# L6790A_GaN.net
KiCad netlist of a schematic drawn in Altium Designer
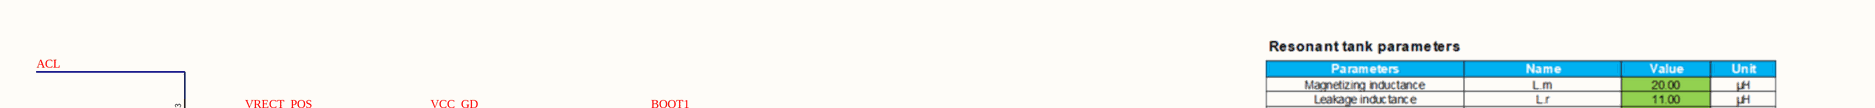
[diagram p0: L6790A_GaN.SchDoc, top left]
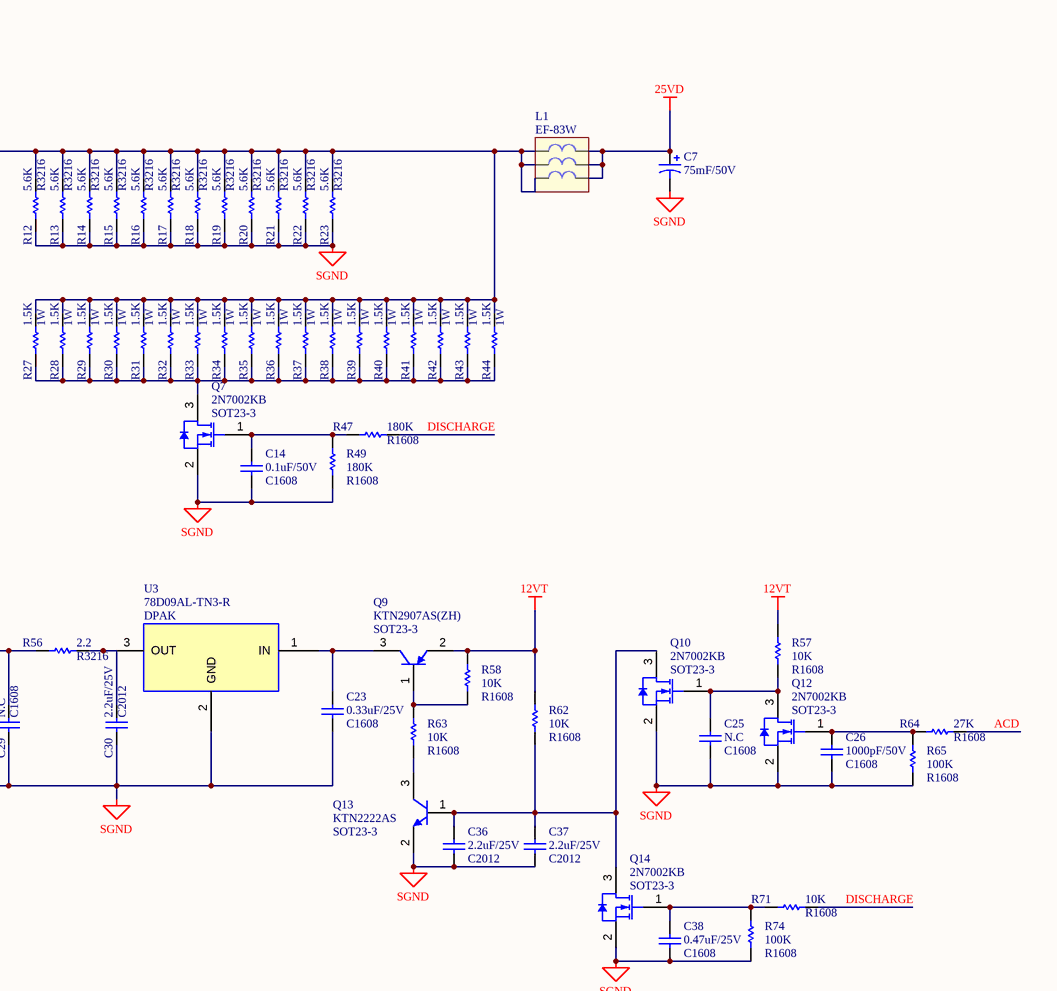
[diagram p1: L6790A_GaN.SchDoc, top right]
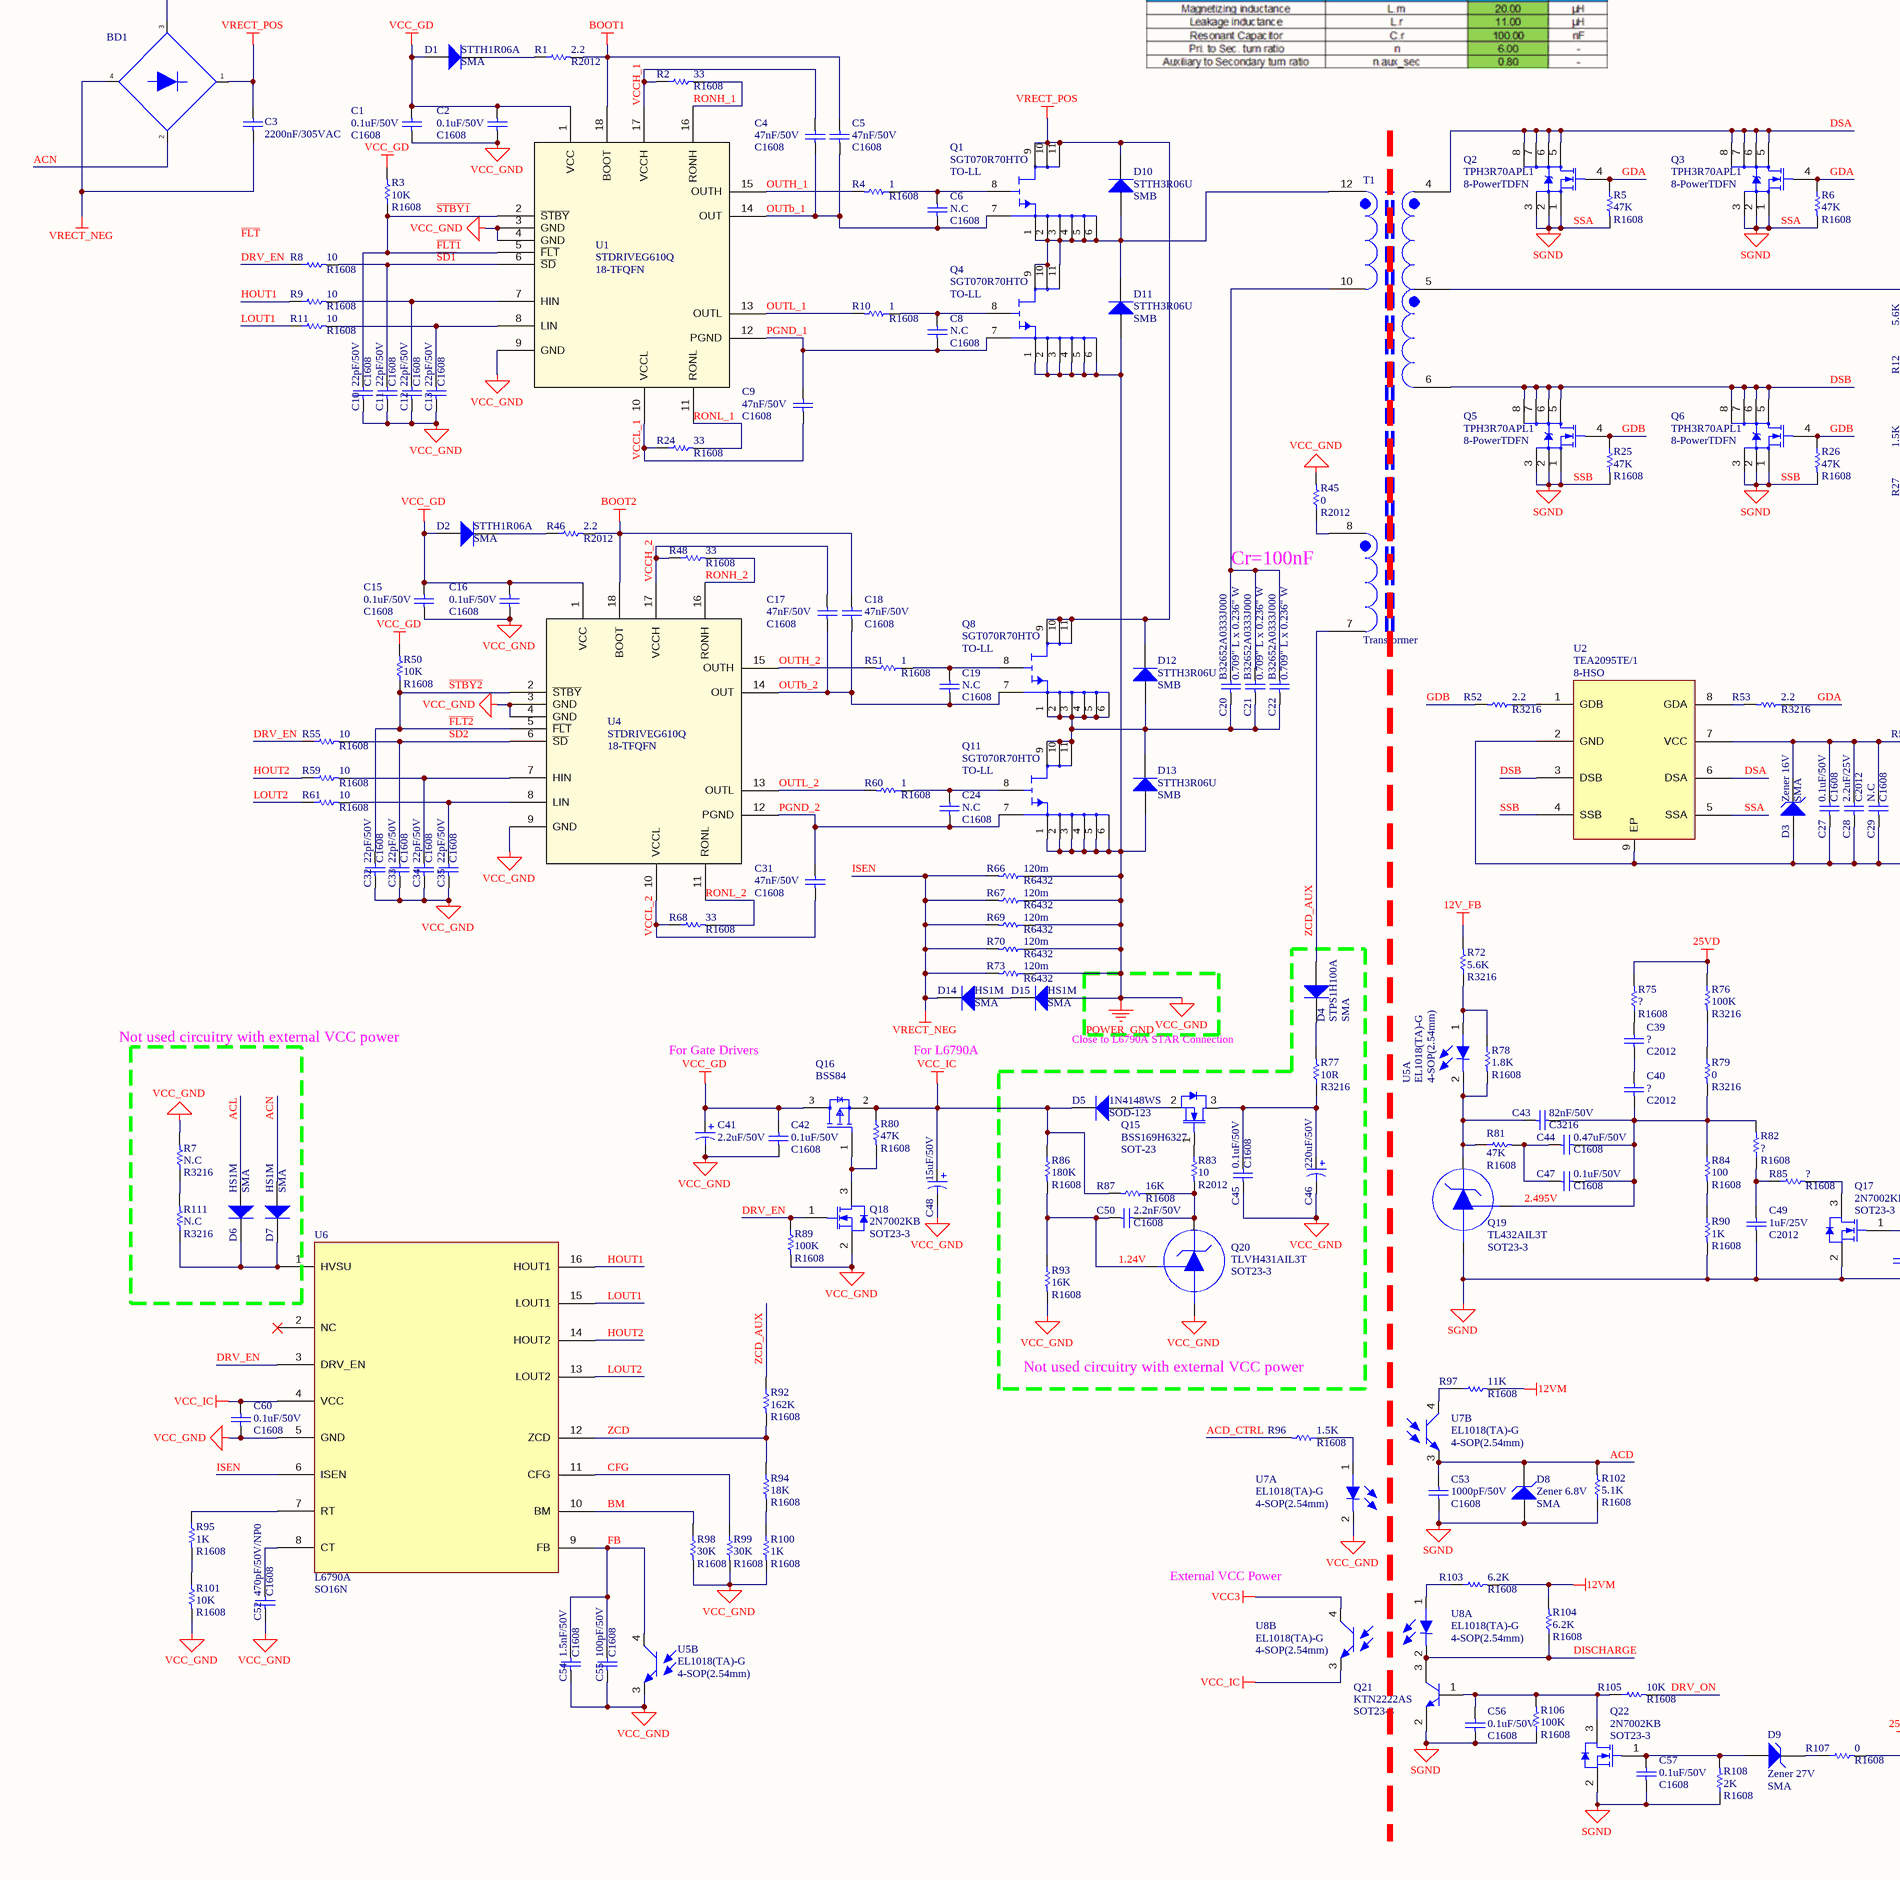
[diagram p2: L6790A_GaN.SchDoc, bottom left]
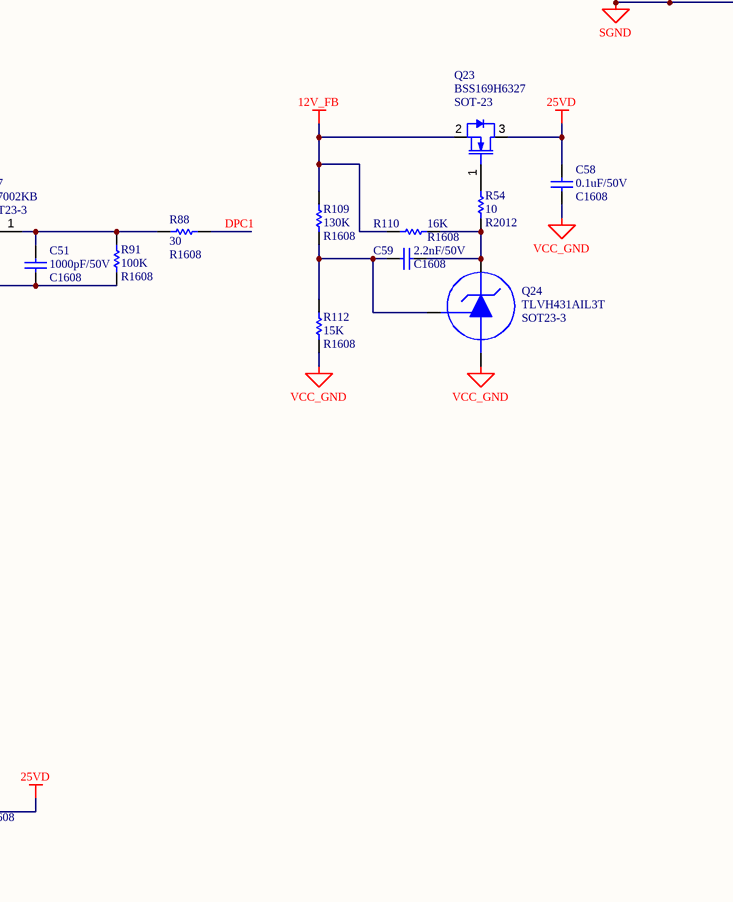
[diagram p3: L6790A_GaN.SchDoc, bottom right]

(export (version "E")
  (design (tool "Eeschema 10.0.6"))
  (components
    (comp (ref "BD1")
      (value "TS6KL60")
      (footprint "2W-DIO-MI-4L-4_6X25X15-7_5P-BD")
      (description "BRIDGE DIODE")
      (libsource (lib "Schematic") (part "BRIDGE"))
    )
    (comp (ref "C1")
      (value "0.1uF/50V")
      (description "Chip MLCC")
      (fields (field (name "PACKAGE/CASE") "C1608"))
      (libsource (lib "Miscellaneous Devices") (part "Cap"))
    )
    (comp (ref "C2")
      (value "0.1uF/50V")
      (description "Chip MLCC")
      (fields (field (name "PACKAGE/CASE") "C1608"))
      (libsource (lib "Miscellaneous Devices") (part "Cap"))
    )
    (comp (ref "C3")
      (value "2200nF/305VAC")
      (description "Chip MLCC")
      (libsource (lib "Miscellaneous Devices") (part "Cap"))
    )
    (comp (ref "C4")
      (value "47nF/50V")
      (description "Chip MLCC")
      (fields (field (name "PACKAGE/CASE") "C1608"))
      (libsource (lib "Miscellaneous Devices") (part "Cap"))
    )
    (comp (ref "C5")
      (value "47nF/50V")
      (description "Chip MLCC")
      (fields (field (name "PACKAGE/CASE") "C1608"))
      (libsource (lib "Miscellaneous Devices") (part "Cap"))
    )
    (comp (ref "C6")
      (value "N.C")
      (description "Chip MLCC")
      (fields (field (name "PACKAGE/CASE") "C1608"))
      (libsource (lib "Miscellaneous Devices") (part "Cap"))
    )
    (comp (ref "C7")
      (value "75mF/50V")
      (footprint "1W-CAP-MI-2L-16DX25-7_5P-EL-F-R1212")
      (description "Electrolytic Capacitor")
      (libsource (lib "Miscellaneous Devices") (part "Cap Pol1"))
    )
    (comp (ref "C8")
      (value "N.C")
      (description "Chip MLCC")
      (fields (field (name "PACKAGE/CASE") "C1608"))
      (libsource (lib "Miscellaneous Devices") (part "Cap"))
    )
    (comp (ref "C9")
      (value "47nF/50V")
      (description "Chip MLCC")
      (fields (field (name "PACKAGE/CASE") "C1608"))
      (libsource (lib "Miscellaneous Devices") (part "Cap"))
    )
    (comp (ref "C10")
      (value "22pF/50V")
      (description "Chip MLCC")
      (fields (field (name "PACKAGE/CASE") "C1608"))
      (libsource (lib "Miscellaneous Devices") (part "Cap"))
    )
    (comp (ref "C11")
      (value "22pF/50V")
      (description "Chip MLCC")
      (fields (field (name "PACKAGE/CASE") "C1608"))
      (libsource (lib "Miscellaneous Devices") (part "Cap"))
    )
    (comp (ref "C12")
      (value "22pF/50V")
      (description "Chip MLCC")
      (fields (field (name "PACKAGE/CASE") "C1608"))
      (libsource (lib "Miscellaneous Devices") (part "Cap"))
    )
    (comp (ref "C13")
      (value "22pF/50V")
      (description "Chip MLCC")
      (fields (field (name "PACKAGE/CASE") "C1608"))
      (libsource (lib "Miscellaneous Devices") (part "Cap"))
    )
    (comp (ref "C14")
      (value "0.1uF/50V")
      (description "Chip MLCC")
      (fields (field (name "PACKAGE/CASE") "C1608"))
      (libsource (lib "Miscellaneous Devices") (part "Cap"))
    )
    (comp (ref "C15")
      (value "0.1uF/50V")
      (description "Chip MLCC")
      (fields (field (name "PACKAGE/CASE") "C1608"))
      (libsource (lib "Miscellaneous Devices") (part "Cap"))
    )
    (comp (ref "C16")
      (value "0.1uF/50V")
      (description "Chip MLCC")
      (fields (field (name "PACKAGE/CASE") "C1608"))
      (libsource (lib "Miscellaneous Devices") (part "Cap"))
    )
    (comp (ref "C17")
      (value "47nF/50V")
      (description "Chip MLCC")
      (fields (field (name "PACKAGE/CASE") "C1608"))
      (libsource (lib "Miscellaneous Devices") (part "Cap"))
    )
    (comp (ref "C18")
      (value "47nF/50V")
      (description "Chip MLCC")
      (fields (field (name "PACKAGE/CASE") "C1608"))
      (libsource (lib "Miscellaneous Devices") (part "Cap"))
    )
    (comp (ref "C19")
      (value "N.C")
      (description "Chip MLCC")
      (fields (field (name "PACKAGE/CASE") "C1608"))
      (libsource (lib "Miscellaneous Devices") (part "Cap"))
    )
    (comp (ref "C20")
      (value "B32652A0333J000")
      (description "Chip MLCC")
      (fields (field (name "PACKAGE/CASE") "0.709\" L x 0.236\" W"))
      (libsource (lib "Miscellaneous Devices") (part "Cap"))
    )
    (comp (ref "C21")
      (value "B32652A0333J000")
      (description "Chip MLCC")
      (fields (field (name "PACKAGE/CASE") "0.709\" L x 0.236\" W"))
      (libsource (lib "Miscellaneous Devices") (part "Cap"))
    )
    (comp (ref "C22")
      (value "B32652A0333J000")
      (description "Chip MLCC")
      (fields (field (name "PACKAGE/CASE") "0.709\" L x 0.236\" W"))
      (libsource (lib "Miscellaneous Devices") (part "Cap"))
    )
    (comp (ref "C23")
      (value "0.33uF/25V")
      (description "Chip MLCC")
      (fields (field (name "PACKAGE/CASE") "C1608"))
      (libsource (lib "Miscellaneous Devices") (part "Cap"))
    )
    (comp (ref "C24")
      (value "N.C")
      (description "Chip MLCC")
      (fields (field (name "PACKAGE/CASE") "C1608"))
      (libsource (lib "Miscellaneous Devices") (part "Cap"))
    )
    (comp (ref "C25")
      (value "N.C")
      (description "Chip MLCC")
      (fields (field (name "PACKAGE/CASE") "C1608"))
      (libsource (lib "Miscellaneous Devices") (part "Cap"))
    )
    (comp (ref "C26")
      (value "1000pF/50V")
      (description "Chip MLCC")
      (fields (field (name "PACKAGE/CASE") "C1608"))
      (libsource (lib "Miscellaneous Devices") (part "Cap"))
    )
    (comp (ref "C27")
      (value "0.1uF/50V")
      (description "Chip MLCC")
      (fields (field (name "PACKAGE/CASE") "C1608"))
      (libsource (lib "Miscellaneous Devices") (part "Cap"))
    )
    (comp (ref "C28")
      (value "2.2uF/25V")
      (description "Chip MLCC")
      (fields (field (name "PACKAGE/CASE") "C2012"))
      (libsource (lib "Miscellaneous Devices") (part "Cap"))
    )
    (comp (ref "C29")
      (value "N.C")
      (description "Chip MLCC")
      (fields (field (name "PACKAGE/CASE") "C1608"))
      (libsource (lib "Miscellaneous Devices") (part "Cap"))
    )
    (comp (ref "C30")
      (value "2.2uF/25V")
      (description "Chip MLCC")
      (fields (field (name "PACKAGE/CASE") "C2012"))
      (libsource (lib "Miscellaneous Devices") (part "Cap"))
    )
    (comp (ref "C31")
      (value "47nF/50V")
      (description "Chip MLCC")
      (fields (field (name "PACKAGE/CASE") "C1608"))
      (libsource (lib "Miscellaneous Devices") (part "Cap"))
    )
    (comp (ref "C32")
      (value "22pF/50V")
      (description "Chip MLCC")
      (fields (field (name "PACKAGE/CASE") "C1608"))
      (libsource (lib "Miscellaneous Devices") (part "Cap"))
    )
    (comp (ref "C33")
      (value "22pF/50V")
      (description "Chip MLCC")
      (fields (field (name "PACKAGE/CASE") "C1608"))
      (libsource (lib "Miscellaneous Devices") (part "Cap"))
    )
    (comp (ref "C34")
      (value "22pF/50V")
      (description "Chip MLCC")
      (fields (field (name "PACKAGE/CASE") "C1608"))
      (libsource (lib "Miscellaneous Devices") (part "Cap"))
    )
    (comp (ref "C35")
      (value "22pF/50V")
      (description "Chip MLCC")
      (fields (field (name "PACKAGE/CASE") "C1608"))
      (libsource (lib "Miscellaneous Devices") (part "Cap"))
    )
    (comp (ref "C36")
      (value "2.2uF/25V")
      (description "Chip MLCC")
      (fields (field (name "PACKAGE/CASE") "C2012"))
      (libsource (lib "Miscellaneous Devices") (part "Cap"))
    )
    (comp (ref "C37")
      (value "2.2uF/25V")
      (description "Chip MLCC")
      (fields (field (name "PACKAGE/CASE") "C2012"))
      (libsource (lib "Miscellaneous Devices") (part "Cap"))
    )
    (comp (ref "C38")
      (value "0.47uF/25V")
      (description "Chip MLCC")
      (fields (field (name "PACKAGE/CASE") "C1608"))
      (libsource (lib "Miscellaneous Devices") (part "Cap"))
    )
    (comp (ref "C39")
      (value "?")
      (description "Chip MLCC")
      (fields (field (name "PACKAGE/CASE") "C2012"))
      (libsource (lib "Miscellaneous Devices") (part "Cap"))
    )
    (comp (ref "C40")
      (value "?")
      (description "Chip MLCC")
      (fields (field (name "PACKAGE/CASE") "C2012"))
      (libsource (lib "Miscellaneous Devices") (part "Cap"))
    )
    (comp (ref "C41")
      (value "2.2uF/50V")
      (footprint "CAP-RA-D5.0H12_5-P2-R0CA")
      (description "Electrolytic Capacitor 33uF/25V")
      (libsource (lib "Miscellaneous Devices") (part "Cap Pol1"))
    )
    (comp (ref "C42")
      (value "0.1uF/50V")
      (description "Chip MLCC")
      (fields (field (name "PACKAGE/CASE") "C1608"))
      (libsource (lib "Miscellaneous Devices") (part "Cap"))
    )
    (comp (ref "C43")
      (value "82nF/50V")
      (footprint "LGP55B_25U1_Y2S:CAP-CHP-3216-R0")
      (description "Chip MLCC")
      (fields (field (name "PACKAGE/CASE") "C3216"))
      (libsource (lib "Miscellaneous Devices") (part "Cap"))
    )
    (comp (ref "C44")
      (value "0.47uF/50V")
      (description "Chip MLCC")
      (fields (field (name "PACKAGE/CASE") "C1608"))
      (libsource (lib "Miscellaneous Devices") (part "Cap"))
    )
    (comp (ref "C45")
      (value "0.1uF/50V")
      (description "Chip MLCC")
      (fields (field (name "PACKAGE/CASE") "C1608"))
      (libsource (lib "Miscellaneous Devices") (part "Cap"))
    )
    (comp (ref "C46")
      (value "220uF/50V")
      (footprint "CAP-RA-D8H5-P2_5-R0")
      (description "Electrolytic Capacitor 22uF/100V")
      (libsource (lib "Miscellaneous Devices") (part "Cap Pol1"))
    )
    (comp (ref "C47")
      (value "0.1uF/50V")
      (description "Chip MLCC")
      (fields (field (name "PACKAGE/CASE") "C1608"))
      (libsource (lib "Miscellaneous Devices") (part "Cap"))
    )
    (comp (ref "C48")
      (value "15uF/50V")
      (footprint "CAP-RA-D5.0H12_5-P2-R0CA")
      (description "Electrolytic Capacitor 33uF/25V")
      (libsource (lib "Miscellaneous Devices") (part "Cap Pol1"))
    )
    (comp (ref "C49")
      (value "1uF/25V")
      (description "Chip MLCC")
      (fields (field (name "PACKAGE/CASE") "C2012"))
      (libsource (lib "Miscellaneous Devices") (part "Cap"))
    )
    (comp (ref "C50")
      (value "2.2nF/50V")
      (description "Chip MLCC")
      (fields (field (name "PACKAGE/CASE") "C1608"))
      (libsource (lib "Miscellaneous Devices") (part "Cap"))
    )
    (comp (ref "C51")
      (value "1000pF/50V")
      (description "Chip MLCC")
      (fields (field (name "PACKAGE/CASE") "C1608"))
      (libsource (lib "Miscellaneous Devices") (part "Cap"))
    )
    (comp (ref "C52")
      (value "470pF/50V/NP0")
      (description "Chip MLCC")
      (fields (field (name "PACKAGE/CASE") "C1608"))
      (libsource (lib "Miscellaneous Devices") (part "Cap"))
    )
    (comp (ref "C53")
      (value "1000pF/50V")
      (description "Chip MLCC")
      (fields (field (name "PACKAGE/CASE") "C1608"))
      (libsource (lib "Miscellaneous Devices") (part "Cap"))
    )
    (comp (ref "C54")
      (value "1.5nF/50V")
      (description "Chip MLCC")
      (fields (field (name "PACKAGE/CASE") "C1608"))
      (libsource (lib "Miscellaneous Devices") (part "Cap"))
    )
    (comp (ref "C55")
      (value "100pF/50V")
      (description "Chip MLCC")
      (fields (field (name "PACKAGE/CASE") "C1608"))
      (libsource (lib "Miscellaneous Devices") (part "Cap"))
    )
    (comp (ref "C56")
      (value "0.1uF/50V")
      (description "Chip MLCC")
      (fields (field (name "PACKAGE/CASE") "C1608"))
      (libsource (lib "Miscellaneous Devices") (part "Cap"))
    )
    (comp (ref "C57")
      (value "0.1uF/50V")
      (description "Chip MLCC")
      (fields (field (name "PACKAGE/CASE") "C1608"))
      (libsource (lib "Miscellaneous Devices") (part "Cap"))
    )
    (comp (ref "C58")
      (value "0.1uF/50V")
      (description "Chip MLCC")
      (fields (field (name "PACKAGE/CASE") "C1608"))
      (libsource (lib "Miscellaneous Devices") (part "Cap"))
    )
    (comp (ref "C59")
      (value "2.2nF/50V")
      (description "Chip MLCC")
      (fields (field (name "PACKAGE/CASE") "C1608"))
      (libsource (lib "Miscellaneous Devices") (part "Cap"))
    )
    (comp (ref "C60")
      (value "0.1uF/50V")
      (description "Chip MLCC")
      (fields (field (name "PACKAGE/CASE") "C1608"))
      (libsource (lib "Miscellaneous Devices") (part "Cap"))
    )
    (comp (ref "D1")
      (value "STTH1R06A")
      (footprint "DIO-SOD123")
      (description "DIODE SCHOTTKY 30V 200MA SOD123")
      (fields (field (name "PACKAGE/CASE") "SMA"))
      (libsource (lib "Miscellaneous Devices") (part "Diode 1N4148"))
    )
    (comp (ref "D2")
      (value "STTH1R06A")
      (footprint "DIO-SOD123")
      (description "DIODE SCHOTTKY 30V 200MA SOD123")
      (fields (field (name "PACKAGE/CASE") "SMA"))
      (libsource (lib "Miscellaneous Devices") (part "Diode 1N4148"))
    )
    (comp (ref "D3")
      (value "Zener 16V")
      (footprint "1W-DIO-CHP-2L-SOD106-SMA")
      (description "DIODE ZENER 30V 1W DO214AC")
      (fields (field (name "PACKAGE/CASE") "SMA"))
      (libsource (lib "Miscellaneous Devices") (part "D Zener"))
    )
    (comp (ref "D4")
      (value "STPS1H100A")
      (footprint "FP-6_560-5005_01-4-IPC_A")
      (description "DIODE STANDARD 200V 200MA SOD80")
      (fields (field (name "PACKAGE/CASE") "SMA"))
      (libsource (lib "Miscellaneous Devices") (part "Diode 1N4148"))
    )
    (comp (ref "D5")
      (value "1N4148WS")
      (footprint "DIO-SOD123")
      (description "DIODE SCHOTTKY 30V 200MA SOD123")
      (fields (field (name "PACKAGE/CASE") "SOD-123"))
      (libsource (lib "Miscellaneous Devices") (part "Diode 1N4148"))
    )
    (comp (ref "D6")
      (value "HS1M")
      (footprint "DIO-SOD123")
      (description "DIODE SCHOTTKY 30V 200MA SOD123")
      (fields (field (name "PACKAGE/CASE") "SMA"))
      (libsource (lib "Miscellaneous Devices") (part "Diode 1N4148"))
    )
    (comp (ref "D7")
      (value "HS1M")
      (footprint "DIO-SOD123")
      (description "DIODE SCHOTTKY 30V 200MA SOD123")
      (fields (field (name "PACKAGE/CASE") "SMA"))
      (libsource (lib "Miscellaneous Devices") (part "Diode 1N4148"))
    )
    (comp (ref "D8")
      (value "Zener 6.8V")
      (footprint "1W-DIO-CHP-2L-SOD106-SMA")
      (description "DIODE ZENER 30V 1W DO214AC")
      (fields (field (name "PACKAGE/CASE") "SMA"))
      (libsource (lib "Miscellaneous Devices") (part "D Zener"))
    )
    (comp (ref "D9")
      (value "Zener 27V")
      (footprint "1W-DIO-CHP-2L-SOD106-SMA")
      (description "DIODE ZENER 30V 1W DO214AC")
      (fields (field (name "PACKAGE/CASE") "SMA"))
      (libsource (lib "Miscellaneous Devices") (part "D Zener"))
    )
    (comp (ref "D10")
      (value "STTH3R06U")
      (footprint "DIO-SOD123")
      (description "DIODE SCHOTTKY 30V 200MA SOD123")
      (fields (field (name "PACKAGE/CASE") "SMB"))
      (libsource (lib "Miscellaneous Devices") (part "Diode 1N4148"))
    )
    (comp (ref "D11")
      (value "STTH3R06U")
      (footprint "DIO-SOD123")
      (description "DIODE SCHOTTKY 30V 200MA SOD123")
      (fields (field (name "PACKAGE/CASE") "SMB"))
      (libsource (lib "Miscellaneous Devices") (part "Diode 1N4148"))
    )
    (comp (ref "D12")
      (value "STTH3R06U")
      (footprint "DIO-SOD123")
      (description "DIODE SCHOTTKY 30V 200MA SOD123")
      (fields (field (name "PACKAGE/CASE") "SMB"))
      (libsource (lib "Miscellaneous Devices") (part "Diode 1N4148"))
    )
    (comp (ref "D13")
      (value "STTH3R06U")
      (footprint "DIO-SOD123")
      (description "DIODE SCHOTTKY 30V 200MA SOD123")
      (fields (field (name "PACKAGE/CASE") "SMB"))
      (libsource (lib "Miscellaneous Devices") (part "Diode 1N4148"))
    )
    (comp (ref "D14")
      (value "HS1M")
      (footprint "DIO-SOD123")
      (description "DIODE SCHOTTKY 30V 200MA SOD123")
      (fields (field (name "PACKAGE/CASE") "SMA"))
      (libsource (lib "Miscellaneous Devices") (part "Diode 1N4148"))
    )
    (comp (ref "D15")
      (value "HS1M")
      (footprint "DIO-SOD123")
      (description "DIODE SCHOTTKY 30V 200MA SOD123")
      (fields (field (name "PACKAGE/CASE") "SMA"))
      (libsource (lib "Miscellaneous Devices") (part "Diode 1N4148"))
    )
    (comp (ref "L1") (value "EF-83W") (libsource (lib "Schematic") (part "EF-83W")))
    (comp (ref "Q1")
      (value "SGT070R70HTO")
      (description "700 V, 53 mΩ typ., 26 A, e-mode PowerGaN transistor")
      (fields (field (name "PACKAGE/CASE") "TO-LL"))
      (libsource (lib "Schematic") (part "SGT070R70HTO"))
    )
    (comp (ref "Q2")
      (value "TPH3R70APL1")
      (description "N-Channel 100 V 90A (Tc) 210W (Tc) Surface Mount 8-SOP Advance (5x5.75)")
      (fields (field (name "PACKAGE/CASE") "8-PowerTDFN"))
      (libsource (lib "Schematic") (part "TPH3R70APL1"))
    )
    (comp (ref "Q3")
      (value "TPH3R70APL1")
      (description "N-Channel 100 V 90A (Tc) 210W (Tc) Surface Mount 8-SOP Advance (5x5.75)")
      (fields (field (name "PACKAGE/CASE") "8-PowerTDFN"))
      (libsource (lib "Schematic") (part "TPH3R70APL1"))
    )
    (comp (ref "Q4")
      (value "SGT070R70HTO")
      (description "700 V, 53 mΩ typ., 26 A, e-mode PowerGaN transistor")
      (fields (field (name "PACKAGE/CASE") "TO-LL"))
      (libsource (lib "Schematic") (part "SGT070R70HTO"))
    )
    (comp (ref "Q5")
      (value "TPH3R70APL1")
      (description "N-Channel 100 V 90A (Tc) 210W (Tc) Surface Mount 8-SOP Advance (5x5.75)")
      (fields (field (name "PACKAGE/CASE") "8-PowerTDFN"))
      (libsource (lib "Schematic") (part "TPH3R70APL1"))
    )
    (comp (ref "Q6")
      (value "TPH3R70APL1")
      (description "N-Channel 100 V 90A (Tc) 210W (Tc) Surface Mount 8-SOP Advance (5x5.75)")
      (fields (field (name "PACKAGE/CASE") "8-PowerTDFN"))
      (libsource (lib "Schematic") (part "TPH3R70APL1"))
    )
    (comp (ref "Q7")
      (value "2N7002KB")
      (description "N-CH MOSFET")
      (fields (field (name "PACKAGE/CASE") "SOT23-3"))
      (libsource (lib "Schematic") (part "2N7002KB"))
    )
    (comp (ref "Q8")
      (value "SGT070R70HTO")
      (description "700 V, 53 mΩ typ., 26 A, e-mode PowerGaN transistor")
      (fields (field (name "PACKAGE/CASE") "TO-LL"))
      (libsource (lib "Schematic") (part "SGT070R70HTO"))
    )
    (comp (ref "Q9")
      (value "KTN2907AS(ZH)")
      (description "PNP BJT")
      (fields (field (name "PACKAGE/CASE") "SOT23-3"))
      (libsource (lib "Schematic") (part "ONSC-PNP-B1E2C3-3"))
    )
    (comp (ref "Q10")
      (value "2N7002KB")
      (description "N-CH MOSFET")
      (fields (field (name "PACKAGE/CASE") "SOT23-3"))
      (libsource (lib "Schematic") (part "2N7002KB"))
    )
    (comp (ref "Q11")
      (value "SGT070R70HTO")
      (description "700 V, 53 mΩ typ., 26 A, e-mode PowerGaN transistor")
      (fields (field (name "PACKAGE/CASE") "TO-LL"))
      (libsource (lib "Schematic") (part "SGT070R70HTO"))
    )
    (comp (ref "Q12")
      (value "2N7002KB")
      (description "N-CH MOSFET")
      (fields (field (name "PACKAGE/CASE") "SOT23-3"))
      (libsource (lib "Schematic") (part "2N7002KB"))
    )
    (comp (ref "Q13")
      (value "KTN2222AS")
      (description "BJT NPN")
      (fields (field (name "PACKAGE/CASE") "SOT23-3"))
      (libsource (lib "Schematic") (part "ONSC-NPN-B1E2C3-3"))
    )
    (comp (ref "Q14")
      (value "2N7002KB")
      (description "N-CH MOSFET")
      (fields (field (name "PACKAGE/CASE") "SOT23-3"))
      (libsource (lib "Schematic") (part "2N7002KB"))
    )
    (comp (ref "Q15")
      (value "BSS169H6327")
      (footprint "SOT-23_TR")
      (description "MOSFET N-CH 100V 170MA SOT23-3")
      (fields (field (name "PACKAGE/CASE") "SOT-23"))
      (libsource (lib "Miscellaneous Devices") (part "CMP-32901-000982-1"))
    )
    (comp (ref "Q16")
      (value "BSS84")
      (footprint "FP-318-08-IPC_A")
      (description "MOSFET P-CH 50V 130MA SOT-23")
      (libsource (lib "Altium Content Vault") (part "1317a8eff0fddff9cd18bdaa032127a"))
    )
    (comp (ref "Q17")
      (value "2N7002KB")
      (description "N-CH MOSFET")
      (fields (field (name "PACKAGE/CASE") "SOT23-3"))
      (libsource (lib "Schematic") (part "2N7002KB"))
    )
    (comp (ref "Q18")
      (value "2N7002KB")
      (description "N-CH MOSFET")
      (fields (field (name "PACKAGE/CASE") "SOT23-3"))
      (libsource (lib "Schematic") (part "2N7002KB"))
    )
    (comp (ref "Q19")
      (value "TL432AIL3T")
      (footprint "SOT-23_TR")
      (description "IC VREF SHUNT ADJ 1% SOT23-3")
      (fields (field (name "PACKAGE/CASE") "SOT23-3"))
      (libsource (lib "*") (part "1W-IC-CHP-3L-SOT23-SCR-R0"))
    )
    (comp (ref "Q20")
      (value "TLVH431AIL3T")
      (footprint "SOT-23_TR")
      (description "IC VREF SHUNT ADJ 1% SOT23-3")
      (fields (field (name "PACKAGE/CASE") "SOT23-3"))
      (libsource (lib "*") (part "1W-IC-CHP-3L-SOT23-SCR-R0"))
    )
    (comp (ref "Q21")
      (value "KTN2222AS")
      (description "BJT NPN")
      (fields (field (name "PACKAGE/CASE") "SOT23-3"))
      (libsource (lib "Schematic") (part "ONSC-NPN-B1E2C3-3"))
    )
    (comp (ref "Q22")
      (value "2N7002KB")
      (description "N-CH MOSFET")
      (fields (field (name "PACKAGE/CASE") "SOT23-3"))
      (libsource (lib "Schematic") (part "2N7002KB"))
    )
    (comp (ref "Q23")
      (value "BSS169H6327")
      (footprint "SOT-23_TR")
      (description "MOSFET N-CH 100V 170MA SOT23-3")
      (fields (field (name "PACKAGE/CASE") "SOT-23"))
      (libsource (lib "Miscellaneous Devices") (part "CMP-32901-000982-1"))
    )
    (comp (ref "Q24")
      (value "TLVH431AIL3T")
      (footprint "SOT-23_TR")
      (description "IC VREF SHUNT ADJ 1% SOT23-3")
      (fields (field (name "PACKAGE/CASE") "SOT23-3"))
      (libsource (lib "*") (part "1W-IC-CHP-3L-SOT23-SCR-R0"))
    )
    (comp (ref "R1")
      (value "2.2")
      (footprint "RES-1608")
      (description "Chip Resistor")
      (fields (field (name "PACKAGE/CASE") "R2012"))
      (libsource (lib "Miscellaneous Devices") (part "Res1"))
    )
    (comp (ref "R2")
      (value "33")
      (footprint "RES-1608")
      (description "Chip Resistor")
      (fields (field (name "PACKAGE/CASE") "R1608"))
      (libsource (lib "Miscellaneous Devices") (part "Res1"))
    )
    (comp (ref "R3")
      (value "10K")
      (footprint "RES-1608")
      (description "Chip Resistor")
      (fields (field (name "PACKAGE/CASE") "R1608"))
      (libsource (lib "Miscellaneous Devices") (part "Res1"))
    )
    (comp (ref "R4")
      (value "1")
      (footprint "RES-1608")
      (description "Chip Resistor")
      (fields (field (name "PACKAGE/CASE") "R1608"))
      (libsource (lib "Miscellaneous Devices") (part "Res1"))
    )
    (comp (ref "R5")
      (value "47K")
      (footprint "RES-1608")
      (description "Chip Resistor")
      (fields (field (name "PACKAGE/CASE") "R1608"))
      (libsource (lib "Miscellaneous Devices") (part "Res1"))
    )
    (comp (ref "R6")
      (value "47K")
      (footprint "RES-1608")
      (description "Chip Resistor")
      (fields (field (name "PACKAGE/CASE") "R1608"))
      (libsource (lib "Miscellaneous Devices") (part "Res1"))
    )
    (comp (ref "R7")
      (value "N.C")
      (footprint "RES-3216")
      (description "Chip Resistor")
      (fields (field (name "PACKAGE/CASE") "R3216"))
      (libsource (lib "Miscellaneous Devices") (part "Res1"))
    )
    (comp (ref "R8")
      (value "10")
      (footprint "RES-1608")
      (description "Chip Resistor")
      (fields (field (name "PACKAGE/CASE") "R1608"))
      (libsource (lib "Miscellaneous Devices") (part "Res1"))
    )
    (comp (ref "R9")
      (value "10")
      (footprint "RES-1608")
      (description "Chip Resistor")
      (fields (field (name "PACKAGE/CASE") "R1608"))
      (libsource (lib "Miscellaneous Devices") (part "Res1"))
    )
    (comp (ref "R10")
      (value "1")
      (footprint "RES-1608")
      (description "Chip Resistor")
      (fields (field (name "PACKAGE/CASE") "R1608"))
      (libsource (lib "Miscellaneous Devices") (part "Res1"))
    )
    (comp (ref "R11")
      (value "10")
      (footprint "RES-1608")
      (description "Chip Resistor")
      (fields (field (name "PACKAGE/CASE") "R1608"))
      (libsource (lib "Miscellaneous Devices") (part "Res1"))
    )
    (comp (ref "R12")
      (value "5.6K")
      (footprint "RES-3216")
      (description "Chip Resistor")
      (fields (field (name "PACKAGE/CASE") "R3216"))
      (libsource (lib "Miscellaneous Devices") (part "Res1"))
    )
    (comp (ref "R13")
      (value "5.6K")
      (footprint "RES-3216")
      (description "Chip Resistor")
      (fields (field (name "PACKAGE/CASE") "R3216"))
      (libsource (lib "Miscellaneous Devices") (part "Res1"))
    )
    (comp (ref "R14")
      (value "5.6K")
      (footprint "RES-3216")
      (description "Chip Resistor")
      (fields (field (name "PACKAGE/CASE") "R3216"))
      (libsource (lib "Miscellaneous Devices") (part "Res1"))
    )
    (comp (ref "R15")
      (value "5.6K")
      (footprint "RES-3216")
      (description "Chip Resistor")
      (fields (field (name "PACKAGE/CASE") "R3216"))
      (libsource (lib "Miscellaneous Devices") (part "Res1"))
    )
    (comp (ref "R16")
      (value "5.6K")
      (footprint "RES-3216")
      (description "Chip Resistor")
      (fields (field (name "PACKAGE/CASE") "R3216"))
      (libsource (lib "Miscellaneous Devices") (part "Res1"))
    )
    (comp (ref "R17")
      (value "5.6K")
      (footprint "RES-3216")
      (description "Chip Resistor")
      (fields (field (name "PACKAGE/CASE") "R3216"))
      (libsource (lib "Miscellaneous Devices") (part "Res1"))
    )
    (comp (ref "R18")
      (value "5.6K")
      (footprint "RES-3216")
      (description "Chip Resistor")
      (fields (field (name "PACKAGE/CASE") "R3216"))
      (libsource (lib "Miscellaneous Devices") (part "Res1"))
    )
    (comp (ref "R19")
      (value "5.6K")
      (footprint "RES-3216")
      (description "Chip Resistor")
      (fields (field (name "PACKAGE/CASE") "R3216"))
      (libsource (lib "Miscellaneous Devices") (part "Res1"))
    )
    (comp (ref "R20")
      (value "5.6K")
      (footprint "RES-3216")
      (description "Chip Resistor")
      (fields (field (name "PACKAGE/CASE") "R3216"))
      (libsource (lib "Miscellaneous Devices") (part "Res1"))
    )
    (comp (ref "R21")
      (value "5.6K")
      (footprint "RES-3216")
      (description "Chip Resistor")
      (fields (field (name "PACKAGE/CASE") "R3216"))
      (libsource (lib "Miscellaneous Devices") (part "Res1"))
    )
    (comp (ref "R22")
      (value "5.6K")
      (footprint "RES-3216")
      (description "Chip Resistor")
      (fields (field (name "PACKAGE/CASE") "R3216"))
      (libsource (lib "Miscellaneous Devices") (part "Res1"))
    )
    (comp (ref "R23")
      (value "5.6K")
      (footprint "RES-3216")
      (description "Chip Resistor")
      (fields (field (name "PACKAGE/CASE") "R3216"))
      (libsource (lib "Miscellaneous Devices") (part "Res1"))
    )
    (comp (ref "R24")
      (value "33")
      (footprint "RES-1608")
      (description "Chip Resistor")
      (fields (field (name "PACKAGE/CASE") "R1608"))
      (libsource (lib "Miscellaneous Devices") (part "Res1"))
    )
    (comp (ref "R25")
      (value "47K")
      (footprint "RES-1608")
      (description "Chip Resistor")
      (fields (field (name "PACKAGE/CASE") "R1608"))
      (libsource (lib "Miscellaneous Devices") (part "Res1"))
    )
    (comp (ref "R26")
      (value "47K")
      (footprint "RES-1608")
      (description "Chip Resistor")
      (fields (field (name "PACKAGE/CASE") "R1608"))
      (libsource (lib "Miscellaneous Devices") (part "Res1"))
    )
    (comp (ref "R27")
      (value "1.5K")
      (description "Watt Resistor")
      (fields (field (name "PACKAGE/CASE") "1W"))
      (libsource (lib "Miscellaneous Devices") (part "Res1"))
    )
    (comp (ref "R28")
      (value "1.5K")
      (description "Watt Resistor")
      (fields (field (name "PACKAGE/CASE") "1W"))
      (libsource (lib "Miscellaneous Devices") (part "Res1"))
    )
    (comp (ref "R29")
      (value "1.5K")
      (description "Watt Resistor")
      (fields (field (name "PACKAGE/CASE") "1W"))
      (libsource (lib "Miscellaneous Devices") (part "Res1"))
    )
    (comp (ref "R30")
      (value "1.5K")
      (description "Watt Resistor")
      (fields (field (name "PACKAGE/CASE") "1W"))
      (libsource (lib "Miscellaneous Devices") (part "Res1"))
    )
    (comp (ref "R31")
      (value "1.5K")
      (description "Watt Resistor")
      (fields (field (name "PACKAGE/CASE") "1W"))
      (libsource (lib "Miscellaneous Devices") (part "Res1"))
    )
    (comp (ref "R32")
      (value "1.5K")
      (description "Watt Resistor")
      (fields (field (name "PACKAGE/CASE") "1W"))
      (libsource (lib "Miscellaneous Devices") (part "Res1"))
    )
    (comp (ref "R33")
      (value "1.5K")
      (description "Watt Resistor")
      (fields (field (name "PACKAGE/CASE") "1W"))
      (libsource (lib "Miscellaneous Devices") (part "Res1"))
    )
    (comp (ref "R34")
      (value "1.5K")
      (description "Watt Resistor")
      (fields (field (name "PACKAGE/CASE") "1W"))
      (libsource (lib "Miscellaneous Devices") (part "Res1"))
    )
    (comp (ref "R35")
      (value "1.5K")
      (description "Watt Resistor")
      (fields (field (name "PACKAGE/CASE") "1W"))
      (libsource (lib "Miscellaneous Devices") (part "Res1"))
    )
    (comp (ref "R36")
      (value "1.5K")
      (description "Watt Resistor")
      (fields (field (name "PACKAGE/CASE") "1W"))
      (libsource (lib "Miscellaneous Devices") (part "Res1"))
    )
    (comp (ref "R37")
      (value "1.5K")
      (description "Watt Resistor")
      (fields (field (name "PACKAGE/CASE") "1W"))
      (libsource (lib "Miscellaneous Devices") (part "Res1"))
    )
    (comp (ref "R38")
      (value "1.5K")
      (description "Watt Resistor")
      (fields (field (name "PACKAGE/CASE") "1W"))
      (libsource (lib "Miscellaneous Devices") (part "Res1"))
    )
    (comp (ref "R39")
      (value "1.5K")
      (description "Watt Resistor")
      (fields (field (name "PACKAGE/CASE") "1W"))
      (libsource (lib "Miscellaneous Devices") (part "Res1"))
    )
    (comp (ref "R40")
      (value "1.5K")
      (description "Watt Resistor")
      (fields (field (name "PACKAGE/CASE") "1W"))
      (libsource (lib "Miscellaneous Devices") (part "Res1"))
    )
    (comp (ref "R41")
      (value "1.5K")
      (description "Watt Resistor")
      (fields (field (name "PACKAGE/CASE") "1W"))
      (libsource (lib "Miscellaneous Devices") (part "Res1"))
    )
    (comp (ref "R42")
      (value "1.5K")
      (description "Watt Resistor")
      (fields (field (name "PACKAGE/CASE") "1W"))
      (libsource (lib "Miscellaneous Devices") (part "Res1"))
    )
    (comp (ref "R43")
      (value "1.5K")
      (description "Watt Resistor")
      (fields (field (name "PACKAGE/CASE") "1W"))
      (libsource (lib "Miscellaneous Devices") (part "Res1"))
    )
    (comp (ref "R44")
      (value "1.5K")
      (description "Watt Resistor")
      (fields (field (name "PACKAGE/CASE") "1W"))
      (libsource (lib "Miscellaneous Devices") (part "Res1"))
    )
    (comp (ref "R45")
      (value "0")
      (footprint "RES-1608")
      (description "Chip Resistor")
      (fields (field (name "PACKAGE/CASE") "R2012"))
      (libsource (lib "Miscellaneous Devices") (part "Res1"))
    )
    (comp (ref "R46")
      (value "2.2")
      (footprint "RES-1608")
      (description "Chip Resistor")
      (fields (field (name "PACKAGE/CASE") "R2012"))
      (libsource (lib "Miscellaneous Devices") (part "Res1"))
    )
    (comp (ref "R47")
      (value "180K")
      (footprint "RES-1608")
      (description "Chip Resistor")
      (fields (field (name "PACKAGE/CASE") "R1608"))
      (libsource (lib "Miscellaneous Devices") (part "Res1"))
    )
    (comp (ref "R48")
      (value "33")
      (footprint "RES-1608")
      (description "Chip Resistor")
      (fields (field (name "PACKAGE/CASE") "R1608"))
      (libsource (lib "Miscellaneous Devices") (part "Res1"))
    )
    (comp (ref "R49")
      (value "180K")
      (footprint "RES-1608")
      (description "Chip Resistor")
      (fields (field (name "PACKAGE/CASE") "R1608"))
      (libsource (lib "Miscellaneous Devices") (part "Res1"))
    )
    (comp (ref "R50")
      (value "10K")
      (footprint "RES-1608")
      (description "Chip Resistor")
      (fields (field (name "PACKAGE/CASE") "R1608"))
      (libsource (lib "Miscellaneous Devices") (part "Res1"))
    )
    (comp (ref "R51")
      (value "1")
      (footprint "RES-1608")
      (description "Chip Resistor")
      (fields (field (name "PACKAGE/CASE") "R1608"))
      (libsource (lib "Miscellaneous Devices") (part "Res1"))
    )
    (comp (ref "R52")
      (value "2.2")
      (footprint "RES-3216")
      (description "Chip Resistor")
      (fields (field (name "PACKAGE/CASE") "R3216"))
      (libsource (lib "Miscellaneous Devices") (part "Res1"))
    )
    (comp (ref "R53")
      (value "2.2")
      (footprint "RES-3216")
      (description "Chip Resistor")
      (fields (field (name "PACKAGE/CASE") "R3216"))
      (libsource (lib "Miscellaneous Devices") (part "Res1"))
    )
    (comp (ref "R54")
      (value "10")
      (footprint "RES-1608")
      (description "Chip Resistor")
      (fields (field (name "PACKAGE/CASE") "R2012"))
      (libsource (lib "Miscellaneous Devices") (part "Res1"))
    )
    (comp (ref "R55")
      (value "10")
      (footprint "RES-1608")
      (description "Chip Resistor")
      (fields (field (name "PACKAGE/CASE") "R1608"))
      (libsource (lib "Miscellaneous Devices") (part "Res1"))
    )
    (comp (ref "R56")
      (value "2.2")
      (footprint "RES-3216")
      (description "Chip Resistor")
      (fields (field (name "PACKAGE/CASE") "R3216"))
      (libsource (lib "Miscellaneous Devices") (part "Res1"))
    )
    (comp (ref "R57")
      (value "10K")
      (footprint "RES-1608")
      (description "Chip Resistor")
      (fields (field (name "PACKAGE/CASE") "R1608"))
      (libsource (lib "Miscellaneous Devices") (part "Res1"))
    )
    (comp (ref "R58")
      (value "10K")
      (footprint "RES-1608")
      (description "Chip Resistor")
      (fields (field (name "PACKAGE/CASE") "R1608"))
      (libsource (lib "Miscellaneous Devices") (part "Res1"))
    )
    (comp (ref "R59")
      (value "10")
      (footprint "RES-1608")
      (description "Chip Resistor")
      (fields (field (name "PACKAGE/CASE") "R1608"))
      (libsource (lib "Miscellaneous Devices") (part "Res1"))
    )
    (comp (ref "R60")
      (value "1")
      (footprint "RES-1608")
      (description "Chip Resistor")
      (fields (field (name "PACKAGE/CASE") "R1608"))
      (libsource (lib "Miscellaneous Devices") (part "Res1"))
    )
    (comp (ref "R61")
      (value "10")
      (footprint "RES-1608")
      (description "Chip Resistor")
      (fields (field (name "PACKAGE/CASE") "R1608"))
      (libsource (lib "Miscellaneous Devices") (part "Res1"))
    )
    (comp (ref "R62")
      (value "10K")
      (footprint "RES-1608")
      (description "Chip Resistor")
      (fields (field (name "PACKAGE/CASE") "R1608"))
      (libsource (lib "Miscellaneous Devices") (part "Res1"))
    )
    (comp (ref "R63")
      (value "10K")
      (footprint "RES-1608")
      (description "Chip Resistor")
      (fields (field (name "PACKAGE/CASE") "R1608"))
      (libsource (lib "Miscellaneous Devices") (part "Res1"))
    )
    (comp (ref "R64")
      (value "27K")
      (footprint "RES-1608")
      (description "Chip Resistor")
      (fields (field (name "PACKAGE/CASE") "R1608"))
      (libsource (lib "Miscellaneous Devices") (part "Res1"))
    )
    (comp (ref "R65")
      (value "100K")
      (footprint "RES-1608")
      (description "Chip Resistor")
      (fields (field (name "PACKAGE/CASE") "R1608"))
      (libsource (lib "Miscellaneous Devices") (part "Res1"))
    )
    (comp (ref "R66")
      (value "120m")
      (description "Chip Resistor")
      (fields (field (name "PACKAGE/CASE") "R6432"))
      (libsource (lib "Miscellaneous Devices") (part "Res1"))
    )
    (comp (ref "R67")
      (value "120m")
      (description "Chip Resistor")
      (fields (field (name "PACKAGE/CASE") "R6432"))
      (libsource (lib "Miscellaneous Devices") (part "Res1"))
    )
    (comp (ref "R68")
      (value "33")
      (footprint "RES-1608")
      (description "Chip Resistor")
      (fields (field (name "PACKAGE/CASE") "R1608"))
      (libsource (lib "Miscellaneous Devices") (part "Res1"))
    )
    (comp (ref "R69")
      (value "120m")
      (description "Chip Resistor")
      (fields (field (name "PACKAGE/CASE") "R6432"))
      (libsource (lib "Miscellaneous Devices") (part "Res1"))
    )
    (comp (ref "R70")
      (value "120m")
      (description "Chip Resistor")
      (fields (field (name "PACKAGE/CASE") "R6432"))
      (libsource (lib "Miscellaneous Devices") (part "Res1"))
    )
    (comp (ref "R71")
      (value "10K")
      (footprint "RES-1608")
      (description "Chip Resistor")
      (fields (field (name "PACKAGE/CASE") "R1608"))
      (libsource (lib "Miscellaneous Devices") (part "Res1"))
    )
    (comp (ref "R72")
      (value "5.6K")
      (footprint "RES-3216")
      (description "Chip Resistor")
      (fields (field (name "PACKAGE/CASE") "R3216"))
      (libsource (lib "Miscellaneous Devices") (part "Res1"))
    )
    (comp (ref "R73")
      (value "120m")
      (description "Chip Resistor")
      (fields (field (name "PACKAGE/CASE") "R6432"))
      (libsource (lib "Miscellaneous Devices") (part "Res1"))
    )
    (comp (ref "R74")
      (value "100K")
      (footprint "RES-1608")
      (description "Chip Resistor")
      (fields (field (name "PACKAGE/CASE") "R1608"))
      (libsource (lib "Miscellaneous Devices") (part "Res1"))
    )
    (comp (ref "R75")
      (value "?")
      (footprint "RES-1608")
      (description "Chip Resistor")
      (fields (field (name "PACKAGE/CASE") "R1608"))
      (libsource (lib "Miscellaneous Devices") (part "Res1"))
    )
    (comp (ref "R76")
      (value "100K")
      (footprint "RES-3216")
      (description "Chip Resistor")
      (fields (field (name "PACKAGE/CASE") "R3216"))
      (libsource (lib "Miscellaneous Devices") (part "Res1"))
    )
    (comp (ref "R77")
      (value "10R")
      (footprint "RES-3216")
      (description "Chip Resistor")
      (fields (field (name "PACKAGE/CASE") "R3216"))
      (libsource (lib "Miscellaneous Devices") (part "Res1"))
    )
    (comp (ref "R78")
      (value "1.8K")
      (footprint "RES-1608")
      (description "Chip Resistor")
      (fields (field (name "PACKAGE/CASE") "R1608"))
      (libsource (lib "Miscellaneous Devices") (part "Res1"))
    )
    (comp (ref "R79")
      (value "0")
      (footprint "RES-3216")
      (description "Chip Resistor")
      (fields (field (name "PACKAGE/CASE") "R3216"))
      (libsource (lib "Miscellaneous Devices") (part "Res1"))
    )
    (comp (ref "R80")
      (value "47K")
      (footprint "RES-1608")
      (description "Chip Resistor")
      (fields (field (name "PACKAGE/CASE") "R1608"))
      (libsource (lib "Miscellaneous Devices") (part "Res1"))
    )
    (comp (ref "R81")
      (value "47K")
      (footprint "RES-1608")
      (description "Chip Resistor")
      (fields (field (name "PACKAGE/CASE") "R1608"))
      (libsource (lib "Miscellaneous Devices") (part "Res1"))
    )
    (comp (ref "R82")
      (value "?")
      (footprint "RES-1608")
      (description "Chip Resistor")
      (fields (field (name "PACKAGE/CASE") "R1608"))
      (libsource (lib "Miscellaneous Devices") (part "Res1"))
    )
    (comp (ref "R83")
      (value "10")
      (footprint "RES-1608")
      (description "Chip Resistor")
      (fields (field (name "PACKAGE/CASE") "R2012"))
      (libsource (lib "Miscellaneous Devices") (part "Res1"))
    )
    (comp (ref "R84")
      (value "100")
      (footprint "RES-1608")
      (description "Chip Resistor")
      (fields (field (name "PACKAGE/CASE") "R1608"))
      (libsource (lib "Miscellaneous Devices") (part "Res1"))
    )
    (comp (ref "R85")
      (value "?")
      (footprint "RES-1608")
      (description "Chip Resistor")
      (fields (field (name "PACKAGE/CASE") "R1608"))
      (libsource (lib "Miscellaneous Devices") (part "Res1"))
    )
    (comp (ref "R86")
      (value "180K")
      (footprint "RES-1608")
      (description "Chip Resistor")
      (fields (field (name "PACKAGE/CASE") "R1608"))
      (libsource (lib "Miscellaneous Devices") (part "Res1"))
    )
    (comp (ref "R87")
      (value "16K")
      (footprint "RES-1608")
      (description "Chip Resistor")
      (fields (field (name "PACKAGE/CASE") "R1608"))
      (libsource (lib "Miscellaneous Devices") (part "Res1"))
    )
    (comp (ref "R88")
      (value "30")
      (footprint "RES-1608")
      (description "Chip Resistor")
      (fields (field (name "PACKAGE/CASE") "R1608"))
      (libsource (lib "Miscellaneous Devices") (part "Res1"))
    )
    (comp (ref "R89")
      (value "100K")
      (footprint "RES-1608")
      (description "Chip Resistor")
      (fields (field (name "PACKAGE/CASE") "R1608"))
      (libsource (lib "Miscellaneous Devices") (part "Res1"))
    )
    (comp (ref "R90")
      (value "1K")
      (footprint "RES-1608")
      (description "Chip Resistor")
      (fields (field (name "PACKAGE/CASE") "R1608"))
      (libsource (lib "Miscellaneous Devices") (part "Res1"))
    )
    (comp (ref "R91")
      (value "100K")
      (footprint "RES-1608")
      (description "Chip Resistor")
      (fields (field (name "PACKAGE/CASE") "R1608"))
      (libsource (lib "Miscellaneous Devices") (part "Res1"))
    )
    (comp (ref "R92")
      (value "162K")
      (footprint "RES-1608")
      (description "Chip Resistor")
      (fields (field (name "PACKAGE/CASE") "R1608"))
      (libsource (lib "Miscellaneous Devices") (part "Res1"))
    )
    (comp (ref "R93")
      (value "16K")
      (footprint "RES-1608")
      (description "Chip Resistor")
      (fields (field (name "PACKAGE/CASE") "R1608"))
      (libsource (lib "Miscellaneous Devices") (part "Res1"))
    )
    (comp (ref "R94")
      (value "18K")
      (footprint "RES-1608")
      (description "Chip Resistor")
      (fields (field (name "PACKAGE/CASE") "R1608"))
      (libsource (lib "Miscellaneous Devices") (part "Res1"))
    )
    (comp (ref "R95")
      (value "1K")
      (footprint "RES-1608")
      (description "Chip Resistor")
      (fields (field (name "PACKAGE/CASE") "R1608"))
      (libsource (lib "Miscellaneous Devices") (part "Res1"))
    )
    (comp (ref "R96")
      (value "1.5K")
      (footprint "RES-1608")
      (description "Chip Resistor")
      (fields (field (name "PACKAGE/CASE") "R1608"))
      (libsource (lib "Miscellaneous Devices") (part "Res1"))
    )
    (comp (ref "R97")
      (value "11K")
      (footprint "RES-1608")
      (description "Chip Resistor")
      (fields (field (name "PACKAGE/CASE") "R1608"))
      (libsource (lib "Miscellaneous Devices") (part "Res1"))
    )
    (comp (ref "R98")
      (value "30K")
      (footprint "RES-1608")
      (description "Chip Resistor")
      (fields (field (name "PACKAGE/CASE") "R1608"))
      (libsource (lib "Miscellaneous Devices") (part "Res1"))
    )
    (comp (ref "R99")
      (value "30K")
      (footprint "RES-1608")
      (description "Chip Resistor")
      (fields (field (name "PACKAGE/CASE") "R1608"))
      (libsource (lib "Miscellaneous Devices") (part "Res1"))
    )
    (comp (ref "R100")
      (value "1K")
      (footprint "RES-1608")
      (description "Chip Resistor")
      (fields (field (name "PACKAGE/CASE") "R1608"))
      (libsource (lib "Miscellaneous Devices") (part "Res1"))
    )
    (comp (ref "R101")
      (value "10K")
      (footprint "RES-1608")
      (description "Chip Resistor")
      (fields (field (name "PACKAGE/CASE") "R1608"))
      (libsource (lib "Miscellaneous Devices") (part "Res1"))
    )
    (comp (ref "R102")
      (value "5.1K")
      (footprint "RES-1608")
      (description "Chip Resistor")
      (fields (field (name "PACKAGE/CASE") "R1608"))
      (libsource (lib "Miscellaneous Devices") (part "Res1"))
    )
    (comp (ref "R103")
      (value "6.2K")
      (footprint "RES-1608")
      (description "Chip Resistor")
      (fields (field (name "PACKAGE/CASE") "R1608"))
      (libsource (lib "Miscellaneous Devices") (part "Res1"))
    )
    (comp (ref "R104")
      (value "6.2K")
      (footprint "RES-1608")
      (description "Chip Resistor")
      (fields (field (name "PACKAGE/CASE") "R1608"))
      (libsource (lib "Miscellaneous Devices") (part "Res1"))
    )
    (comp (ref "R105")
      (value "10K")
      (footprint "RES-1608")
      (description "Chip Resistor")
      (fields (field (name "PACKAGE/CASE") "R1608"))
      (libsource (lib "Miscellaneous Devices") (part "Res1"))
    )
    (comp (ref "R106")
      (value "100K")
      (footprint "RES-1608")
      (description "Chip Resistor")
      (fields (field (name "PACKAGE/CASE") "R1608"))
      (libsource (lib "Miscellaneous Devices") (part "Res1"))
    )
    (comp (ref "R107")
      (value "0")
      (footprint "RES-1608")
      (description "Chip Resistor")
      (fields (field (name "PACKAGE/CASE") "R1608"))
      (libsource (lib "Miscellaneous Devices") (part "Res1"))
    )
    (comp (ref "R108")
      (value "2K")
      (footprint "RES-1608")
      (description "Chip Resistor")
      (fields (field (name "PACKAGE/CASE") "R1608"))
      (libsource (lib "Miscellaneous Devices") (part "Res1"))
    )
    (comp (ref "R109")
      (value "130K")
      (footprint "RES-1608")
      (description "Chip Resistor")
      (fields (field (name "PACKAGE/CASE") "R1608"))
      (libsource (lib "Miscellaneous Devices") (part "Res1"))
    )
    (comp (ref "R110")
      (value "16K")
      (footprint "RES-1608")
      (description "Chip Resistor")
      (fields (field (name "PACKAGE/CASE") "R1608"))
      (libsource (lib "Miscellaneous Devices") (part "Res1"))
    )
    (comp (ref "R111")
      (value "N.C")
      (footprint "RES-3216")
      (description "Chip Resistor")
      (fields (field (name "PACKAGE/CASE") "R3216"))
      (libsource (lib "Miscellaneous Devices") (part "Res1"))
    )
    (comp (ref "R112")
      (value "15K")
      (footprint "RES-1608")
      (description "Chip Resistor")
      (fields (field (name "PACKAGE/CASE") "R1608"))
      (libsource (lib "Miscellaneous Devices") (part "Res1"))
    )
    (comp (ref "T1") (value "Transformer") (libsource (lib "Schematic") (part "Transformer")))
    (comp (ref "U1")
      (value "STDRIVEG610Q")
      (description "High voltage and high-speed half-bridge gate driver for GaN power switches")
      (fields (field (name "PACKAGE/CASE") "18-TFQFN"))
      (libsource (lib "Schematic") (part "STDRIVEG610Q"))
    )
    (comp (ref "U2")
      (value "TEA2095TE/1")
      (description "LLC SR CONTROLLER IC")
      (fields (field (name "PACKAGE/CASE") "8-HSO"))
      (libsource (lib "Schematic") (part "TEA2095TE/1"))
    )
    (comp (ref "U3")
      (value "78D09AL-TN3-R")
      (description "3-TERMINALS 1A POSITIVE VOLTAGE REGULATOR")
      (fields (field (name "PACKAGE/CASE") "DPAK"))
      (libsource (lib "Schematic") (part "78D09AL-TN3-R"))
    )
    (comp (ref "U4")
      (value "STDRIVEG610Q")
      (description "High voltage and high-speed half-bridge gate driver for GaN power switches")
      (fields (field (name "PACKAGE/CASE") "18-TFQFN"))
      (libsource (lib "Schematic") (part "STDRIVEG610Q"))
    )
    (comp (ref "U5")
      (value "EL1018(TA)-G")
      (footprint "1W-IC-CHP-4L-3_6X7_6-2_54P-L10_2-PC")
      (description "Photocoupler")
      (fields (field (name "PACKAGE/CASE") "4-SOP(2.54mm)"))
      (libsource (lib "SFH617A-2X019T") (part "SFH617A-2X019T"))
    )
    (comp (ref "U6")
      (value "L6790A")
      (description "LLC-PFC controller IC for insulated power factor corrector application")
      (fields (field (name "PACKAGE/CASE") "SO16N"))
      (libsource (lib "Schematic") (part "L6790A"))
    )
    (comp (ref "U7")
      (value "EL1018(TA)-G")
      (footprint "1W-IC-CHP-4L-3_6X7_6-2_54P-L10_2-PC")
      (description "Photocoupler")
      (fields (field (name "PACKAGE/CASE") "4-SOP(2.54mm)"))
      (libsource (lib "Schematic") (part "SFH617A-2X019T"))
    )
    (comp (ref "U8")
      (value "EL1018(TA)-G")
      (footprint "1W-IC-CHP-4L-3_6X7_6-2_54P-L10_2-PC")
      (description "Photocoupler")
      (fields (field (name "PACKAGE/CASE") "4-SOP(2.54mm)"))
      (libsource (lib "Schematic") (part "SFH617A-2X019T"))
    )
  )
  (nets
    (net (code "1") (name "/1.24V") (class "Default")
      (node (ref "C50") (pin "1") (pinfunction "1_1") (pintype "passive"))
      (node (ref "Q20") (pin "1") (pinfunction "R_1") (pintype "passive"))
      (node (ref "R86") (pin "2") (pinfunction "2_2") (pintype "passive"))
      (node (ref "R93") (pin "1") (pinfunction "1_1") (pintype "passive"))
    )
    (net (code "2") (name "/2.495V") (class "Default")
      (node (ref "C40") (pin "2") (pinfunction "2_2") (pintype "passive"))
      (node (ref "C43") (pin "1") (pinfunction "1_1") (pintype "passive"))
      (node (ref "C44") (pin "1") (pinfunction "1_1") (pintype "passive"))
      (node (ref "C47") (pin "1") (pinfunction "1_1") (pintype "passive"))
      (node (ref "Q19") (pin "1") (pinfunction "R_1") (pintype "passive"))
      (node (ref "R79") (pin "2") (pinfunction "2_2") (pintype "passive"))
      (node (ref "R82") (pin "2") (pinfunction "2_2") (pintype "passive"))
      (node (ref "R84") (pin "1") (pinfunction "1_1") (pintype "passive"))
    )
    (net (code "3") (name "/ACD") (class "Default")
      (node (ref "C53") (pin "1") (pinfunction "1_1") (pintype "passive"))
      (node (ref "D8") (pin "2") (pinfunction "K_2") (pintype "passive"))
      (node (ref "R102") (pin "2") (pinfunction "2_2") (pintype "passive"))
      (node (ref "R64") (pin "2") (pinfunction "2_2") (pintype "passive"))
      (node (ref "U7") (pin "3") (pinfunction "E_3") (pintype "passive"))
    )
    (net (code "4") (name "/ACD_CTRL") (class "Default")
      (node (ref "R96") (pin "2") (pinfunction "2_2") (pintype "passive"))
    )
    (net (code "5") (name "/ACL") (class "Default")
      (node (ref "BD1") (pin "3") (pinfunction "3_3") (pintype "passive"))
      (node (ref "D6") (pin "1") (pinfunction "A_1") (pintype "passive"))
    )
    (net (code "6") (name "/ACN") (class "Default")
      (node (ref "BD1") (pin "2") (pinfunction "2_2") (pintype "passive"))
      (node (ref "D7") (pin "1") (pinfunction "A_1") (pintype "passive"))
    )
    (net (code "7") (name "/BM") (class "Default")
      (node (ref "R98") (pin "1") (pinfunction "1_1") (pintype "passive"))
      (node (ref "U6") (pin "10") (pinfunction "BM_10") (pintype "passive"))
    )
    (net (code "8") (name "/CFG") (class "Default")
      (node (ref "R99") (pin "1") (pinfunction "1_1") (pintype "passive"))
      (node (ref "U6") (pin "11") (pinfunction "CFG_11") (pintype "passive"))
    )
    (net (code "9") (name "/DISCHARGE") (class "Default")
      (node (ref "Q21") (pin "3") (pinfunction "C_3") (pintype "passive"))
      (node (ref "R104") (pin "1") (pinfunction "1_1") (pintype "passive"))
      (node (ref "R47") (pin "2") (pinfunction "2_2") (pintype "passive"))
      (node (ref "R71") (pin "2") (pinfunction "2_2") (pintype "passive"))
      (node (ref "U8") (pin "2") (pinfunction "C_2") (pintype "passive"))
    )
    (net (code "10") (name "/DPC1") (class "Default")
      (node (ref "R88") (pin "2") (pinfunction "2_2") (pintype "passive"))
    )
    (net (code "11") (name "/DRV_EN") (class "Default")
      (node (ref "Q18") (pin "1") (pinfunction "G_1") (pintype "passive"))
      (node (ref "R55") (pin "1") (pinfunction "1_1") (pintype "passive"))
      (node (ref "R8") (pin "1") (pinfunction "1_1") (pintype "passive"))
      (node (ref "R89") (pin "1") (pinfunction "1_1") (pintype "passive"))
      (node (ref "U6") (pin "3") (pinfunction "DRV_EN_3") (pintype "passive"))
    )
    (net (code "12") (name "/DRV_ON") (class "Default")
      (node (ref "R105") (pin "2") (pinfunction "2_2") (pintype "passive"))
    )
    (net (code "13") (name "/DSA") (class "Default")
      (node (ref "Q2") (pin "5") (pinfunction "D_5") (pintype "passive"))
      (node (ref "Q2") (pin "6") (pinfunction "D_6") (pintype "passive"))
      (node (ref "Q2") (pin "7") (pinfunction "D_7") (pintype "passive"))
      (node (ref "Q2") (pin "8") (pinfunction "D_8") (pintype "passive"))
      (node (ref "Q3") (pin "5") (pinfunction "D_5") (pintype "passive"))
      (node (ref "Q3") (pin "6") (pinfunction "D_6") (pintype "passive"))
      (node (ref "Q3") (pin "7") (pinfunction "D_7") (pintype "passive"))
      (node (ref "Q3") (pin "8") (pinfunction "D_8") (pintype "passive"))
      (node (ref "T1") (pin "4") (pinfunction "4_4") (pintype "passive"))
      (node (ref "U2") (pin "6") (pinfunction "DSA_6") (pintype "passive"))
    )
    (net (code "14") (name "/DSB") (class "Default")
      (node (ref "Q5") (pin "5") (pinfunction "D_5") (pintype "passive"))
      (node (ref "Q5") (pin "6") (pinfunction "D_6") (pintype "passive"))
      (node (ref "Q5") (pin "7") (pinfunction "D_7") (pintype "passive"))
      (node (ref "Q5") (pin "8") (pinfunction "D_8") (pintype "passive"))
      (node (ref "Q6") (pin "5") (pinfunction "D_5") (pintype "passive"))
      (node (ref "Q6") (pin "6") (pinfunction "D_6") (pintype "passive"))
      (node (ref "Q6") (pin "7") (pinfunction "D_7") (pintype "passive"))
      (node (ref "Q6") (pin "8") (pinfunction "D_8") (pintype "passive"))
      (node (ref "T1") (pin "6") (pinfunction "6_6") (pintype "passive"))
      (node (ref "U2") (pin "3") (pinfunction "DSB_3") (pintype "passive"))
    )
    (net (code "15") (name "/FB") (class "Default")
      (node (ref "C54") (pin "1") (pinfunction "1_1") (pintype "passive"))
      (node (ref "C55") (pin "1") (pinfunction "1_1") (pintype "passive"))
      (node (ref "U5") (pin "4") (pinfunction "C_4") (pintype "passive"))
      (node (ref "U6") (pin "9") (pinfunction "FB_9") (pintype "passive"))
    )
    (net (code "17") (name "/FLT1") (class "Default")
      (node (ref "C10") (pin "1") (pinfunction "1_1") (pintype "passive"))
      (node (ref "R3") (pin "1") (pinfunction "1_1") (pintype "passive"))
      (node (ref "U1") (pin "2") (pinfunction "STBY_2") (pintype "passive"))
      (node (ref "U1") (pin "5") (pinfunction "FLT_5") (pintype "passive"))
    )
    (net (code "18") (name "/FLT2") (class "Default")
      (node (ref "C32") (pin "1") (pinfunction "1_1") (pintype "passive"))
      (node (ref "R50") (pin "1") (pinfunction "1_1") (pintype "passive"))
      (node (ref "U4") (pin "2") (pinfunction "STBY_2") (pintype "passive"))
      (node (ref "U4") (pin "5") (pinfunction "FLT_5") (pintype "passive"))
    )
    (net (code "19") (name "/GDA") (class "Default")
      (node (ref "Q2") (pin "4") (pinfunction "G_4") (pintype "passive"))
      (node (ref "Q3") (pin "4") (pinfunction "G_4") (pintype "passive"))
      (node (ref "R5") (pin "1") (pinfunction "1_1") (pintype "passive"))
      (node (ref "R53") (pin "1") (pinfunction "1_1") (pintype "passive"))
      (node (ref "R6") (pin "1") (pinfunction "1_1") (pintype "passive"))
    )
    (net (code "20") (name "/GDB") (class "Default")
      (node (ref "Q5") (pin "4") (pinfunction "G_4") (pintype "passive"))
      (node (ref "Q6") (pin "4") (pinfunction "G_4") (pintype "passive"))
      (node (ref "R25") (pin "1") (pinfunction "1_1") (pintype "passive"))
      (node (ref "R26") (pin "1") (pinfunction "1_1") (pintype "passive"))
      (node (ref "R52") (pin "2") (pinfunction "2_2") (pintype "passive"))
    )
    (net (code "21") (name "/HOUT1") (class "Default")
      (node (ref "R9") (pin "1") (pinfunction "1_1") (pintype "passive"))
      (node (ref "U6") (pin "16") (pinfunction "HOUT1_16") (pintype "passive"))
    )
    (net (code "22") (name "/HOUT2") (class "Default")
      (node (ref "R59") (pin "1") (pinfunction "1_1") (pintype "passive"))
      (node (ref "U6") (pin "14") (pinfunction "HOUT2_14") (pintype "passive"))
    )
    (net (code "23") (name "/LOUT1") (class "Default")
      (node (ref "R11") (pin "1") (pinfunction "1_1") (pintype "passive"))
      (node (ref "U6") (pin "15") (pinfunction "LOUT1_15") (pintype "passive"))
    )
    (net (code "24") (name "/LOUT2") (class "Default")
      (node (ref "R61") (pin "1") (pinfunction "1_1") (pintype "passive"))
      (node (ref "U6") (pin "13") (pinfunction "LOUT2_13") (pintype "passive"))
    )
    (net (code "25") (name "/OUTH_1") (class "Default")
      (node (ref "R4") (pin "2") (pinfunction "2_2") (pintype "passive"))
      (node (ref "U1") (pin "15") (pinfunction "OUTH_15") (pintype "passive"))
    )
    (net (code "26") (name "/OUTH_2") (class "Default")
      (node (ref "R51") (pin "2") (pinfunction "2_2") (pintype "passive"))
      (node (ref "U4") (pin "15") (pinfunction "OUTH_15") (pintype "passive"))
    )
    (net (code "27") (name "/OUTL_1") (class "Default")
      (node (ref "R10") (pin "2") (pinfunction "2_2") (pintype "passive"))
      (node (ref "U1") (pin "13") (pinfunction "OUTL_13") (pintype "passive"))
    )
    (net (code "28") (name "/OUTL_2") (class "Default")
      (node (ref "R60") (pin "2") (pinfunction "2_2") (pintype "passive"))
      (node (ref "U4") (pin "13") (pinfunction "OUTL_13") (pintype "passive"))
    )
    (net (code "29") (name "/OUTb_1") (class "Default")
      (node (ref "C4") (pin "2") (pinfunction "2_2") (pintype "passive"))
      (node (ref "C5") (pin "2") (pinfunction "2_2") (pintype "passive"))
      (node (ref "C6") (pin "2") (pinfunction "2_2") (pintype "passive"))
      (node (ref "Q1") (pin "7") (pinfunction "KS_7") (pintype "passive"))
      (node (ref "U1") (pin "14") (pinfunction "OUT_14") (pintype "passive"))
    )
    (net (code "30") (name "/OUTb_2") (class "Default")
      (node (ref "C17") (pin "2") (pinfunction "2_2") (pintype "passive"))
      (node (ref "C18") (pin "2") (pinfunction "2_2") (pintype "passive"))
      (node (ref "C19") (pin "2") (pinfunction "2_2") (pintype "passive"))
      (node (ref "Q8") (pin "7") (pinfunction "KS_7") (pintype "passive"))
      (node (ref "U4") (pin "14") (pinfunction "OUT_14") (pintype "passive"))
    )
    (net (code "31") (name "/PGND_1") (class "Default")
      (node (ref "C8") (pin "2") (pinfunction "2_2") (pintype "passive"))
      (node (ref "C9") (pin "1") (pinfunction "1_1") (pintype "passive"))
      (node (ref "Q4") (pin "7") (pinfunction "KS_7") (pintype "passive"))
      (node (ref "U1") (pin "12") (pinfunction "PGND_12") (pintype "passive"))
    )
    (net (code "32") (name "/PGND_2") (class "Default")
      (node (ref "C24") (pin "2") (pinfunction "2_2") (pintype "passive"))
      (node (ref "C31") (pin "1") (pinfunction "1_1") (pintype "passive"))
      (node (ref "Q11") (pin "7") (pinfunction "KS_7") (pintype "passive"))
      (node (ref "U4") (pin "12") (pinfunction "PGND_12") (pintype "passive"))
    )
    (net (code "33") (name "/RONH_1") (class "Default")
      (node (ref "R2") (pin "2") (pinfunction "2_2") (pintype "passive"))
      (node (ref "U1") (pin "16") (pinfunction "RONH_16") (pintype "passive"))
    )
    (net (code "34") (name "/RONH_2") (class "Default")
      (node (ref "R48") (pin "2") (pinfunction "2_2") (pintype "passive"))
      (node (ref "U4") (pin "16") (pinfunction "RONH_16") (pintype "passive"))
    )
    (net (code "35") (name "/RONL_1") (class "Default")
      (node (ref "R24") (pin "2") (pinfunction "2_2") (pintype "passive"))
      (node (ref "U1") (pin "11") (pinfunction "RONL_11") (pintype "passive"))
    )
    (net (code "36") (name "/RONL_2") (class "Default")
      (node (ref "R68") (pin "2") (pinfunction "2_2") (pintype "passive"))
      (node (ref "U4") (pin "11") (pinfunction "RONL_11") (pintype "passive"))
    )
    (net (code "37") (name "/SD1") (class "Default")
      (node (ref "C11") (pin "1") (pinfunction "1_1") (pintype "passive"))
      (node (ref "R8") (pin "2") (pinfunction "2_2") (pintype "passive"))
      (node (ref "U1") (pin "6") (pinfunction "SD_6") (pintype "passive"))
    )
    (net (code "38") (name "/SD2") (class "Default")
      (node (ref "C33") (pin "1") (pinfunction "1_1") (pintype "passive"))
      (node (ref "R55") (pin "2") (pinfunction "2_2") (pintype "passive"))
      (node (ref "U4") (pin "6") (pinfunction "SD_6") (pintype "passive"))
    )
    (net (code "39") (name "/VCCH_1") (class "Default")
      (node (ref "C4") (pin "1") (pinfunction "1_1") (pintype "passive"))
      (node (ref "R2") (pin "1") (pinfunction "1_1") (pintype "passive"))
      (node (ref "U1") (pin "17") (pinfunction "VCCH_17") (pintype "passive"))
    )
    (net (code "40") (name "/VCCH_2") (class "Default")
      (node (ref "C17") (pin "1") (pinfunction "1_1") (pintype "passive"))
      (node (ref "R48") (pin "1") (pinfunction "1_1") (pintype "passive"))
      (node (ref "U4") (pin "17") (pinfunction "VCCH_17") (pintype "passive"))
    )
    (net (code "41") (name "/VCCL_1") (class "Default")
      (node (ref "C9") (pin "2") (pinfunction "2_2") (pintype "passive"))
      (node (ref "R24") (pin "1") (pinfunction "1_1") (pintype "passive"))
      (node (ref "U1") (pin "10") (pinfunction "VCCL_10") (pintype "passive"))
    )
    (net (code "42") (name "/VCCL_2") (class "Default")
      (node (ref "C31") (pin "2") (pinfunction "2_2") (pintype "passive"))
      (node (ref "R68") (pin "1") (pinfunction "1_1") (pintype "passive"))
      (node (ref "U4") (pin "10") (pinfunction "VCCL_10") (pintype "passive"))
    )
    (net (code "43") (name "/ZCD") (class "Default")
      (node (ref "R92") (pin "2") (pinfunction "2_2") (pintype "passive"))
      (node (ref "R94") (pin "1") (pinfunction "1_1") (pintype "passive"))
      (node (ref "U6") (pin "12") (pinfunction "ZCD_12") (pintype "passive"))
    )
    (net (code "44") (name "/ZCD_AUX") (class "Default")
      (node (ref "D4") (pin "1") (pinfunction "A_1") (pintype "passive"))
      (node (ref "R92") (pin "1") (pinfunction "1_1") (pintype "passive"))
      (node (ref "T1") (pin "7") (pinfunction "7_7") (pintype "passive"))
    )
    (net (code "45") (name "12VM") (class "Default")
      (node (ref "R103") (pin "2") (pinfunction "2_2") (pintype "passive"))
      (node (ref "R104") (pin "2") (pinfunction "2_2") (pintype "passive"))
      (node (ref "R97") (pin "2") (pinfunction "2_2") (pintype "passive"))
    )
    (net (code "46") (name "12VT") (class "Default")
      (node (ref "Q9") (pin "2") (pinfunction "E_2") (pintype "passive"))
      (node (ref "R57") (pin "1") (pinfunction "1_1") (pintype "passive"))
      (node (ref "R58") (pin "1") (pinfunction "1_1") (pintype "passive"))
      (node (ref "R62") (pin "1") (pinfunction "1_1") (pintype "passive"))
    )
    (net (code "47") (name "12V_FB") (class "Default")
      (node (ref "Q23") (pin "2") (pinfunction "SOURCE_2") (pintype "passive"))
      (node (ref "R109") (pin "1") (pinfunction "1_1") (pintype "passive"))
      (node (ref "R110") (pin "2") (pinfunction "2_2") (pintype "passive"))
      (node (ref "R72") (pin "2") (pinfunction "2_2") (pintype "passive"))
    )
    (net (code "48") (name "25VD") (class "Default")
      (node (ref "C58") (pin "1") (pinfunction "1_1") (pintype "passive"))
      (node (ref "C7") (pin "1") (pinfunction "1_1") (pintype "passive"))
      (node (ref "L1") (pin "2") (pinfunction "2_2") (pintype "passive"))
      (node (ref "Q23") (pin "3") (pinfunction "DRAIN_3") (pintype "passive"))
      (node (ref "R107") (pin "2") (pinfunction "2_2") (pintype "passive"))
      (node (ref "R75") (pin "2") (pinfunction "2_2") (pintype "passive"))
      (node (ref "R76") (pin "1") (pinfunction "1_1") (pintype "passive"))
    )
    (net (code "49") (name "BOOT1") (class "Default")
      (node (ref "C5") (pin "1") (pinfunction "1_1") (pintype "passive"))
      (node (ref "R1") (pin "2") (pinfunction "2_2") (pintype "passive"))
      (node (ref "U1") (pin "18") (pinfunction "BOOT_18") (pintype "passive"))
    )
    (net (code "50") (name "BOOT2") (class "Default")
      (node (ref "C18") (pin "1") (pinfunction "1_1") (pintype "passive"))
      (node (ref "R46") (pin "2") (pinfunction "2_2") (pintype "passive"))
      (node (ref "U4") (pin "18") (pinfunction "BOOT_18") (pintype "passive"))
    )
    (net (code "51") (name "Net-(C20-Pad1)") (class "Default")
      (node (ref "C20") (pin "1") (pinfunction "1_1") (pintype "passive"))
      (node (ref "C21") (pin "1") (pinfunction "1_1") (pintype "passive"))
      (node (ref "C22") (pin "1") (pinfunction "1_1") (pintype "passive"))
      (node (ref "T1") (pin "10") (pinfunction "10_10") (pintype "passive"))
    )
    (net (code "52") (name "Net-(C39-Pad1)") (class "Default")
      (node (ref "C39") (pin "1") (pinfunction "1_1") (pintype "passive"))
      (node (ref "R75") (pin "1") (pinfunction "1_1") (pintype "passive"))
    )
    (net (code "53") (name "Net-(C39-Pad2)") (class "Default")
      (node (ref "C39") (pin "2") (pinfunction "2_2") (pintype "passive"))
      (node (ref "C40") (pin "1") (pinfunction "1_1") (pintype "passive"))
    )
    (net (code "54") (name "Net-(C44-Pad2)") (class "Default")
      (node (ref "C44") (pin "2") (pinfunction "2_2") (pintype "passive"))
      (node (ref "C47") (pin "2") (pinfunction "2_2") (pintype "passive"))
      (node (ref "R81") (pin "2") (pinfunction "2_2") (pintype "passive"))
    )
    (net (code "55") (name "Net-(C49-Pad1)") (class "Default")
      (node (ref "C49") (pin "1") (pinfunction "1_1") (pintype "passive"))
      (node (ref "R82") (pin "1") (pinfunction "1_1") (pintype "passive"))
      (node (ref "R85") (pin "1") (pinfunction "1_1") (pintype "passive"))
    )
    (net (code "56") (name "Net-(D1-K)") (class "Default")
      (node (ref "D1") (pin "2") (pinfunction "K_2") (pintype "passive"))
      (node (ref "R1") (pin "1") (pinfunction "1_1") (pintype "passive"))
    )
    (net (code "57") (name "Net-(D2-K)") (class "Default")
      (node (ref "D2") (pin "2") (pinfunction "K_2") (pintype "passive"))
      (node (ref "R46") (pin "1") (pinfunction "1_1") (pintype "passive"))
    )
    (net (code "58") (name "Net-(D3-K)") (class "Default")
      (node (ref "C27") (pin "1") (pinfunction "1_1") (pintype "passive"))
      (node (ref "C28") (pin "1") (pinfunction "1_1") (pintype "passive"))
      (node (ref "C29") (pin "1") (pinfunction "1_1") (pintype "passive"))
      (node (ref "D3") (pin "2") (pinfunction "K_2") (pintype "passive"))
      (node (ref "R56") (pin "2") (pinfunction "2_2") (pintype "passive"))
      (node (ref "U2") (pin "7") (pinfunction "VCC_7") (pintype "passive"))
    )
    (net (code "59") (name "Net-(D4-K)") (class "Default")
      (node (ref "D4") (pin "2") (pinfunction "K_2") (pintype "passive"))
      (node (ref "R77") (pin "2") (pinfunction "2_2") (pintype "passive"))
    )
    (net (code "60") (name "Net-(D5-A)") (class "Default")
      (node (ref "D5") (pin "1") (pinfunction "A_1") (pintype "passive"))
      (node (ref "Q15") (pin "2") (pinfunction "SOURCE_2") (pintype "passive"))
    )
    (net (code "61") (name "Net-(D6-K)") (class "Default")
      (node (ref "D6") (pin "2") (pinfunction "K_2") (pintype "passive"))
      (node (ref "D7") (pin "2") (pinfunction "K_2") (pintype "passive"))
      (node (ref "R111") (pin "1") (pinfunction "1_1") (pintype "passive"))
      (node (ref "U6") (pin "1") (pinfunction "HVSU_1") (pintype "passive"))
    )
    (net (code "62") (name "Net-(D9-A)") (class "Default")
      (node (ref "C57") (pin "2") (pinfunction "2_2") (pintype "passive"))
      (node (ref "D9") (pin "1") (pinfunction "A_1") (pintype "passive"))
      (node (ref "Q22") (pin "1") (pinfunction "G_1") (pintype "passive"))
      (node (ref "R108") (pin "2") (pinfunction "2_2") (pintype "passive"))
    )
    (net (code "63") (name "Net-(D9-K)") (class "Default")
      (node (ref "D9") (pin "2") (pinfunction "K_2") (pintype "passive"))
      (node (ref "R107") (pin "1") (pinfunction "1_1") (pintype "passive"))
    )
    (net (code "64") (name "Net-(D10-A)") (class "Default")
      (node (ref "D10") (pin "1") (pinfunction "A_1") (pintype "passive"))
      (node (ref "D11") (pin "2") (pinfunction "K_2") (pintype "passive"))
      (node (ref "Q1") (pin "1") (pinfunction "S_1") (pintype "passive"))
      (node (ref "Q1") (pin "2") (pinfunction "S_2") (pintype "passive"))
      (node (ref "Q1") (pin "3") (pinfunction "S_3") (pintype "passive"))
      (node (ref "Q1") (pin "4") (pinfunction "S_4") (pintype "passive"))
      (node (ref "Q1") (pin "5") (pinfunction "S_5") (pintype "passive"))
      (node (ref "Q1") (pin "6") (pinfunction "S_6") (pintype "passive"))
      (node (ref "Q4") (pin "10") (pinfunction "D_10") (pintype "passive"))
      (node (ref "Q4") (pin "11") (pinfunction "D_11") (pintype "passive"))
      (node (ref "Q4") (pin "9") (pinfunction "D_9") (pintype "passive"))
      (node (ref "T1") (pin "12") (pinfunction "12_12") (pintype "passive"))
    )
    (net (code "65") (name "Net-(D12-A)") (class "Default")
      (node (ref "C20") (pin "2") (pinfunction "2_2") (pintype "passive"))
      (node (ref "C21") (pin "2") (pinfunction "2_2") (pintype "passive"))
      (node (ref "C22") (pin "2") (pinfunction "2_2") (pintype "passive"))
      (node (ref "D12") (pin "1") (pinfunction "A_1") (pintype "passive"))
      (node (ref "D13") (pin "2") (pinfunction "K_2") (pintype "passive"))
      (node (ref "Q11") (pin "10") (pinfunction "D_10") (pintype "passive"))
      (node (ref "Q11") (pin "11") (pinfunction "D_11") (pintype "passive"))
      (node (ref "Q11") (pin "9") (pinfunction "D_9") (pintype "passive"))
      (node (ref "Q8") (pin "1") (pinfunction "S_1") (pintype "passive"))
      (node (ref "Q8") (pin "2") (pinfunction "S_2") (pintype "passive"))
      (node (ref "Q8") (pin "3") (pinfunction "S_3") (pintype "passive"))
      (node (ref "Q8") (pin "4") (pinfunction "S_4") (pintype "passive"))
      (node (ref "Q8") (pin "5") (pinfunction "S_5") (pintype "passive"))
      (node (ref "Q8") (pin "6") (pinfunction "S_6") (pintype "passive"))
    )
    (net (code "66") (name "Net-(D14-A)") (class "Default")
      (node (ref "D14") (pin "1") (pinfunction "A_1") (pintype "passive"))
      (node (ref "D15") (pin "2") (pinfunction "K_2") (pintype "passive"))
    )
    (net (code "67") (name "Net-(L1-Pad1)") (class "Default")
      (node (ref "L1") (pin "1") (pinfunction "1_1") (pintype "passive"))
      (node (ref "R12") (pin "2") (pinfunction "2_2") (pintype "passive"))
      (node (ref "R13") (pin "2") (pinfunction "2_2") (pintype "passive"))
      (node (ref "R14") (pin "2") (pinfunction "2_2") (pintype "passive"))
      (node (ref "R15") (pin "2") (pinfunction "2_2") (pintype "passive"))
      (node (ref "R16") (pin "2") (pinfunction "2_2") (pintype "passive"))
      (node (ref "R17") (pin "2") (pinfunction "2_2") (pintype "passive"))
      (node (ref "R18") (pin "2") (pinfunction "2_2") (pintype "passive"))
      (node (ref "R19") (pin "2") (pinfunction "2_2") (pintype "passive"))
      (node (ref "R20") (pin "2") (pinfunction "2_2") (pintype "passive"))
      (node (ref "R21") (pin "2") (pinfunction "2_2") (pintype "passive"))
      (node (ref "R22") (pin "2") (pinfunction "2_2") (pintype "passive"))
      (node (ref "R23") (pin "2") (pinfunction "2_2") (pintype "passive"))
      (node (ref "R27") (pin "2") (pinfunction "2_2") (pintype "passive"))
      (node (ref "R28") (pin "2") (pinfunction "2_2") (pintype "passive"))
      (node (ref "R29") (pin "2") (pinfunction "2_2") (pintype "passive"))
      (node (ref "R30") (pin "2") (pinfunction "2_2") (pintype "passive"))
      (node (ref "R31") (pin "2") (pinfunction "2_2") (pintype "passive"))
      (node (ref "R32") (pin "2") (pinfunction "2_2") (pintype "passive"))
      (node (ref "R33") (pin "2") (pinfunction "2_2") (pintype "passive"))
      (node (ref "R34") (pin "2") (pinfunction "2_2") (pintype "passive"))
      (node (ref "R35") (pin "2") (pinfunction "2_2") (pintype "passive"))
      (node (ref "R36") (pin "2") (pinfunction "2_2") (pintype "passive"))
      (node (ref "R37") (pin "2") (pinfunction "2_2") (pintype "passive"))
      (node (ref "R38") (pin "2") (pinfunction "2_2") (pintype "passive"))
      (node (ref "R39") (pin "2") (pinfunction "2_2") (pintype "passive"))
      (node (ref "R40") (pin "2") (pinfunction "2_2") (pintype "passive"))
      (node (ref "R41") (pin "2") (pinfunction "2_2") (pintype "passive"))
      (node (ref "R42") (pin "2") (pinfunction "2_2") (pintype "passive"))
      (node (ref "R43") (pin "2") (pinfunction "2_2") (pintype "passive"))
      (node (ref "R44") (pin "2") (pinfunction "2_2") (pintype "passive"))
      (node (ref "T1") (pin "5") (pinfunction "5_5") (pintype "passive"))
    )
    (net (code "68") (name "Net-(Q1-G)") (class "Default")
      (node (ref "C6") (pin "1") (pinfunction "1_1") (pintype "passive"))
      (node (ref "Q1") (pin "8") (pinfunction "G_8") (pintype "passive"))
      (node (ref "R4") (pin "1") (pinfunction "1_1") (pintype "passive"))
    )
    (net (code "69") (name "Net-(Q4-G)") (class "Default")
      (node (ref "C8") (pin "1") (pinfunction "1_1") (pintype "passive"))
      (node (ref "Q4") (pin "8") (pinfunction "G_8") (pintype "passive"))
      (node (ref "R10") (pin "1") (pinfunction "1_1") (pintype "passive"))
    )
    (net (code "70") (name "Net-(Q7-D)") (class "Default")
      (node (ref "Q7") (pin "3") (pinfunction "D_3") (pintype "passive"))
      (node (ref "R27") (pin "1") (pinfunction "1_1") (pintype "passive"))
      (node (ref "R28") (pin "1") (pinfunction "1_1") (pintype "passive"))
      (node (ref "R29") (pin "1") (pinfunction "1_1") (pintype "passive"))
      (node (ref "R30") (pin "1") (pinfunction "1_1") (pintype "passive"))
      (node (ref "R31") (pin "1") (pinfunction "1_1") (pintype "passive"))
      (node (ref "R32") (pin "1") (pinfunction "1_1") (pintype "passive"))
      (node (ref "R33") (pin "1") (pinfunction "1_1") (pintype "passive"))
      (node (ref "R34") (pin "1") (pinfunction "1_1") (pintype "passive"))
      (node (ref "R35") (pin "1") (pinfunction "1_1") (pintype "passive"))
      (node (ref "R36") (pin "1") (pinfunction "1_1") (pintype "passive"))
      (node (ref "R37") (pin "1") (pinfunction "1_1") (pintype "passive"))
      (node (ref "R38") (pin "1") (pinfunction "1_1") (pintype "passive"))
      (node (ref "R39") (pin "1") (pinfunction "1_1") (pintype "passive"))
      (node (ref "R40") (pin "1") (pinfunction "1_1") (pintype "passive"))
      (node (ref "R41") (pin "1") (pinfunction "1_1") (pintype "passive"))
      (node (ref "R42") (pin "1") (pinfunction "1_1") (pintype "passive"))
      (node (ref "R43") (pin "1") (pinfunction "1_1") (pintype "passive"))
      (node (ref "R44") (pin "1") (pinfunction "1_1") (pintype "passive"))
    )
    (net (code "71") (name "Net-(Q7-G)") (class "Default")
      (node (ref "C14") (pin "1") (pinfunction "1_1") (pintype "passive"))
      (node (ref "Q7") (pin "1") (pinfunction "G_1") (pintype "passive"))
      (node (ref "R47") (pin "1") (pinfunction "1_1") (pintype "passive"))
      (node (ref "R49") (pin "1") (pinfunction "1_1") (pintype "passive"))
    )
    (net (code "72") (name "Net-(Q8-G)") (class "Default")
      (node (ref "C19") (pin "1") (pinfunction "1_1") (pintype "passive"))
      (node (ref "Q8") (pin "8") (pinfunction "G_8") (pintype "passive"))
      (node (ref "R51") (pin "1") (pinfunction "1_1") (pintype "passive"))
    )
    (net (code "73") (name "Net-(Q9-B)") (class "Default")
      (node (ref "Q9") (pin "1") (pinfunction "B_1") (pintype "passive"))
      (node (ref "R58") (pin "2") (pinfunction "2_2") (pintype "passive"))
      (node (ref "R63") (pin "1") (pinfunction "1_1") (pintype "passive"))
    )
    (net (code "74") (name "Net-(Q9-C)") (class "Default")
      (node (ref "C23") (pin "1") (pinfunction "1_1") (pintype "passive"))
      (node (ref "Q9") (pin "3") (pinfunction "C_3") (pintype "passive"))
      (node (ref "U3") (pin "1") (pinfunction "IN_1") (pintype "passive"))
    )
    (net (code "75") (name "Net-(Q10-D)") (class "Default")
      (node (ref "C36") (pin "1") (pinfunction "1_1") (pintype "passive"))
      (node (ref "C37") (pin "1") (pinfunction "1_1") (pintype "passive"))
      (node (ref "Q10") (pin "3") (pinfunction "D_3") (pintype "passive"))
      (node (ref "Q13") (pin "1") (pinfunction "B_1") (pintype "passive"))
      (node (ref "Q14") (pin "3") (pinfunction "D_3") (pintype "passive"))
      (node (ref "R62") (pin "2") (pinfunction "2_2") (pintype "passive"))
    )
    (net (code "76") (name "Net-(Q10-G)") (class "Default")
      (node (ref "C25") (pin "1") (pinfunction "1_1") (pintype "passive"))
      (node (ref "Q10") (pin "1") (pinfunction "G_1") (pintype "passive"))
      (node (ref "Q12") (pin "3") (pinfunction "D_3") (pintype "passive"))
      (node (ref "R57") (pin "2") (pinfunction "2_2") (pintype "passive"))
    )
    (net (code "77") (name "Net-(Q11-G)") (class "Default")
      (node (ref "C24") (pin "1") (pinfunction "1_1") (pintype "passive"))
      (node (ref "Q11") (pin "8") (pinfunction "G_8") (pintype "passive"))
      (node (ref "R60") (pin "1") (pinfunction "1_1") (pintype "passive"))
    )
    (net (code "78") (name "Net-(Q12-G)") (class "Default")
      (node (ref "C26") (pin "1") (pinfunction "1_1") (pintype "passive"))
      (node (ref "Q12") (pin "1") (pinfunction "G_1") (pintype "passive"))
      (node (ref "R64") (pin "1") (pinfunction "1_1") (pintype "passive"))
      (node (ref "R65") (pin "1") (pinfunction "1_1") (pintype "passive"))
    )
    (net (code "79") (name "Net-(Q13-C)") (class "Default")
      (node (ref "Q13") (pin "3") (pinfunction "C_3") (pintype "passive"))
      (node (ref "R63") (pin "2") (pinfunction "2_2") (pintype "passive"))
    )
    (net (code "80") (name "Net-(Q14-G)") (class "Default")
      (node (ref "C38") (pin "1") (pinfunction "1_1") (pintype "passive"))
      (node (ref "Q14") (pin "1") (pinfunction "G_1") (pintype "passive"))
      (node (ref "R71") (pin "1") (pinfunction "1_1") (pintype "passive"))
      (node (ref "R74") (pin "1") (pinfunction "1_1") (pintype "passive"))
    )
    (net (code "81") (name "Net-(Q15-DRAIN)") (class "Default")
      (node (ref "C45") (pin "1") (pinfunction "1_1") (pintype "passive"))
      (node (ref "C46") (pin "1") (pinfunction "1_1") (pintype "passive"))
      (node (ref "Q15") (pin "3") (pinfunction "DRAIN_3") (pintype "passive"))
      (node (ref "R77") (pin "1") (pinfunction "1_1") (pintype "passive"))
    )
    (net (code "82") (name "Net-(Q15-GATE)") (class "Default")
      (node (ref "Q15") (pin "1") (pinfunction "GATE_1") (pintype "passive"))
      (node (ref "R83") (pin "1") (pinfunction "1_1") (pintype "passive"))
    )
    (net (code "83") (name "Net-(Q16-G)") (class "Default")
      (node (ref "Q16") (pin "1") (pinfunction "G_1") (pintype "passive"))
      (node (ref "Q18") (pin "3") (pinfunction "D_3") (pintype "passive"))
      (node (ref "R80") (pin "2") (pinfunction "2_2") (pintype "passive"))
    )
    (net (code "84") (name "Net-(Q17-D)") (class "Default")
      (node (ref "Q17") (pin "3") (pinfunction "D_3") (pintype "passive"))
      (node (ref "R85") (pin "2") (pinfunction "2_2") (pintype "passive"))
    )
    (net (code "85") (name "Net-(Q17-G)") (class "Default")
      (node (ref "C51") (pin "1") (pinfunction "1_1") (pintype "passive"))
      (node (ref "Q17") (pin "1") (pinfunction "G_1") (pintype "passive"))
      (node (ref "R88") (pin "1") (pinfunction "1_1") (pintype "passive"))
      (node (ref "R91") (pin "2") (pinfunction "2_2") (pintype "passive"))
    )
    (net (code "86") (name "Net-(Q19-K)") (class "Default")
      (node (ref "C43") (pin "2") (pinfunction "2_2") (pintype "passive"))
      (node (ref "Q19") (pin "2") (pinfunction "K_2") (pintype "passive"))
      (node (ref "R78") (pin "2") (pinfunction "2_2") (pintype "passive"))
      (node (ref "R81") (pin "1") (pinfunction "1_1") (pintype "passive"))
      (node (ref "U5") (pin "2") (pinfunction "C_2") (pintype "passive"))
    )
    (net (code "87") (name "Net-(Q20-K)") (class "Default")
      (node (ref "C50") (pin "2") (pinfunction "2_2") (pintype "passive"))
      (node (ref "Q20") (pin "2") (pinfunction "K_2") (pintype "passive"))
      (node (ref "R83") (pin "2") (pinfunction "2_2") (pintype "passive"))
      (node (ref "R87") (pin "1") (pinfunction "1_1") (pintype "passive"))
    )
    (net (code "88") (name "Net-(Q21-B)") (class "Default")
      (node (ref "C56") (pin "2") (pinfunction "2_2") (pintype "passive"))
      (node (ref "Q21") (pin "1") (pinfunction "B_1") (pintype "passive"))
      (node (ref "Q22") (pin "3") (pinfunction "D_3") (pintype "passive"))
      (node (ref "R105") (pin "1") (pinfunction "1_1") (pintype "passive"))
      (node (ref "R106") (pin "2") (pinfunction "2_2") (pintype "passive"))
    )
    (net (code "89") (name "Net-(Q23-GATE)") (class "Default")
      (node (ref "Q23") (pin "1") (pinfunction "GATE_1") (pintype "passive"))
      (node (ref "R54") (pin "1") (pinfunction "1_1") (pintype "passive"))
    )
    (net (code "90") (name "Net-(Q24-K)") (class "Default")
      (node (ref "C59") (pin "2") (pinfunction "2_2") (pintype "passive"))
      (node (ref "Q24") (pin "2") (pinfunction "K_2") (pintype "passive"))
      (node (ref "R110") (pin "1") (pinfunction "1_1") (pintype "passive"))
      (node (ref "R54") (pin "2") (pinfunction "2_2") (pintype "passive"))
    )
    (net (code "91") (name "Net-(Q24-R)") (class "Default")
      (node (ref "C59") (pin "1") (pinfunction "1_1") (pintype "passive"))
      (node (ref "Q24") (pin "1") (pinfunction "R_1") (pintype "passive"))
      (node (ref "R109") (pin "2") (pinfunction "2_2") (pintype "passive"))
      (node (ref "R112") (pin "1") (pinfunction "1_1") (pintype "passive"))
    )
    (net (code "92") (name "Net-(R45-Pad1)") (class "Default")
      (node (ref "R45") (pin "1") (pinfunction "1_1") (pintype "passive"))
      (node (ref "T1") (pin "8") (pinfunction "8_8") (pintype "passive"))
    )
    (net (code "93") (name "Net-(R76-Pad2)") (class "Default")
      (node (ref "R76") (pin "2") (pinfunction "2_2") (pintype "passive"))
      (node (ref "R79") (pin "1") (pinfunction "1_1") (pintype "passive"))
    )
    (net (code "94") (name "Net-(R84-Pad2)") (class "Default")
      (node (ref "R84") (pin "2") (pinfunction "2_2") (pintype "passive"))
      (node (ref "R90") (pin "1") (pinfunction "1_1") (pintype "passive"))
    )
    (net (code "95") (name "Net-(R100-Pad1)") (class "Default")
      (node (ref "R100") (pin "1") (pinfunction "1_1") (pintype "passive"))
      (node (ref "R94") (pin "2") (pinfunction "2_2") (pintype "passive"))
    )
    (net (code "96") (name "Net-(R101-Pad1)") (class "Default")
      (node (ref "R101") (pin "1") (pinfunction "1_1") (pintype "passive"))
      (node (ref "R95") (pin "2") (pinfunction "2_2") (pintype "passive"))
    )
    (net (code "97") (name "Net-(R111-Pad2)") (class "Default")
      (node (ref "R111") (pin "2") (pinfunction "2_2") (pintype "passive"))
      (node (ref "R7") (pin "1") (pinfunction "1_1") (pintype "passive"))
    )
    (net (code "98") (name "Net-(U1-HIN)") (class "Default")
      (node (ref "C12") (pin "1") (pinfunction "1_1") (pintype "passive"))
      (node (ref "R9") (pin "2") (pinfunction "2_2") (pintype "passive"))
      (node (ref "U1") (pin "7") (pinfunction "HIN_7") (pintype "passive"))
    )
    (net (code "99") (name "Net-(U1-LIN)") (class "Default")
      (node (ref "C13") (pin "1") (pinfunction "1_1") (pintype "passive"))
      (node (ref "R11") (pin "2") (pinfunction "2_2") (pintype "passive"))
      (node (ref "U1") (pin "8") (pinfunction "LIN_8") (pintype "passive"))
    )
    (net (code "100") (name "Net-(U2-GDA)") (class "Default")
      (node (ref "R53") (pin "2") (pinfunction "2_2") (pintype "passive"))
      (node (ref "U2") (pin "8") (pinfunction "GDA_8") (pintype "passive"))
    )
    (net (code "101") (name "Net-(U2-GDB)") (class "Default")
      (node (ref "R52") (pin "1") (pinfunction "1_1") (pintype "passive"))
      (node (ref "U2") (pin "1") (pinfunction "GDB_1") (pintype "passive"))
    )
    (net (code "102") (name "Net-(U3-OUT)") (class "Default")
      (node (ref "C30") (pin "1") (pinfunction "1_1") (pintype "passive"))
      (node (ref "R56") (pin "1") (pinfunction "1_1") (pintype "passive"))
      (node (ref "U3") (pin "3") (pinfunction "OUT_3") (pintype "passive"))
    )
    (net (code "103") (name "Net-(U4-HIN)") (class "Default")
      (node (ref "C34") (pin "1") (pinfunction "1_1") (pintype "passive"))
      (node (ref "R59") (pin "2") (pinfunction "2_2") (pintype "passive"))
      (node (ref "U4") (pin "7") (pinfunction "HIN_7") (pintype "passive"))
    )
    (net (code "104") (name "Net-(U4-LIN)") (class "Default")
      (node (ref "C35") (pin "1") (pinfunction "1_1") (pintype "passive"))
      (node (ref "R61") (pin "2") (pinfunction "2_2") (pintype "passive"))
      (node (ref "U4") (pin "8") (pinfunction "LIN_8") (pintype "passive"))
    )
    (net (code "105") (name "Net-(U5A-A)") (class "Default")
      (node (ref "R72") (pin "1") (pinfunction "1_1") (pintype "passive"))
      (node (ref "R78") (pin "1") (pinfunction "1_1") (pintype "passive"))
      (node (ref "U5") (pin "1") (pinfunction "A_1") (pintype "passive"))
    )
    (net (code "106") (name "Net-(U6-CT)") (class "Default")
      (node (ref "C52") (pin "1") (pinfunction "1_1") (pintype "passive"))
      (node (ref "U6") (pin "8") (pinfunction "CT_8") (pintype "passive"))
    )
    (net (code "107") (name "Net-(U6-RT)") (class "Default")
      (node (ref "R95") (pin "1") (pinfunction "1_1") (pintype "passive"))
      (node (ref "U6") (pin "7") (pinfunction "RT_7") (pintype "passive"))
    )
    (net (code "108") (name "Net-(U7A-A)") (class "Default")
      (node (ref "R96") (pin "1") (pinfunction "1_1") (pintype "passive"))
      (node (ref "U7") (pin "1") (pinfunction "A_1") (pintype "passive"))
    )
    (net (code "109") (name "Net-(U7B-C)") (class "Default")
      (node (ref "R97") (pin "1") (pinfunction "1_1") (pintype "passive"))
      (node (ref "U7") (pin "4") (pinfunction "C_4") (pintype "passive"))
    )
    (net (code "110") (name "Net-(U8A-A)") (class "Default")
      (node (ref "R103") (pin "1") (pinfunction "1_1") (pintype "passive"))
      (node (ref "U8") (pin "1") (pinfunction "A_1") (pintype "passive"))
    )
    (net (code "111") (name "POWER_GND") (class "Default")
      (node (ref "C1") (pin "2") (pinfunction "2_2") (pintype "passive"))
      (node (ref "C10") (pin "2") (pinfunction "2_2") (pintype "passive"))
      (node (ref "C11") (pin "2") (pinfunction "2_2") (pintype "passive"))
      (node (ref "C12") (pin "2") (pinfunction "2_2") (pintype "passive"))
      (node (ref "C13") (pin "2") (pinfunction "2_2") (pintype "passive"))
      (node (ref "C15") (pin "2") (pinfunction "2_2") (pintype "passive"))
      (node (ref "C16") (pin "2") (pinfunction "2_2") (pintype "passive"))
      (node (ref "C2") (pin "2") (pinfunction "2_2") (pintype "passive"))
      (node (ref "C32") (pin "2") (pinfunction "2_2") (pintype "passive"))
      (node (ref "C33") (pin "2") (pinfunction "2_2") (pintype "passive"))
      (node (ref "C34") (pin "2") (pinfunction "2_2") (pintype "passive"))
      (node (ref "C35") (pin "2") (pinfunction "2_2") (pintype "passive"))
      (node (ref "C41") (pin "2") (pinfunction "2_2") (pintype "passive"))
      (node (ref "C42") (pin "2") (pinfunction "2_2") (pintype "passive"))
      (node (ref "C45") (pin "2") (pinfunction "2_2") (pintype "passive"))
      (node (ref "C46") (pin "2") (pinfunction "2_2") (pintype "passive"))
      (node (ref "C48") (pin "2") (pinfunction "2_2") (pintype "passive"))
      (node (ref "C52") (pin "2") (pinfunction "2_2") (pintype "passive"))
      (node (ref "C54") (pin "2") (pinfunction "2_2") (pintype "passive"))
      (node (ref "C55") (pin "2") (pinfunction "2_2") (pintype "passive"))
      (node (ref "C58") (pin "2") (pinfunction "2_2") (pintype "passive"))
      (node (ref "C60") (pin "2") (pinfunction "2_2") (pintype "passive"))
      (node (ref "D11") (pin "1") (pinfunction "A_1") (pintype "passive"))
      (node (ref "D13") (pin "1") (pinfunction "A_1") (pintype "passive"))
      (node (ref "D15") (pin "1") (pinfunction "A_1") (pintype "passive"))
      (node (ref "Q11") (pin "1") (pinfunction "S_1") (pintype "passive"))
      (node (ref "Q11") (pin "2") (pinfunction "S_2") (pintype "passive"))
      (node (ref "Q11") (pin "3") (pinfunction "S_3") (pintype "passive"))
      (node (ref "Q11") (pin "4") (pinfunction "S_4") (pintype "passive"))
      (node (ref "Q11") (pin "5") (pinfunction "S_5") (pintype "passive"))
      (node (ref "Q11") (pin "6") (pinfunction "S_6") (pintype "passive"))
      (node (ref "Q18") (pin "2") (pinfunction "S_2") (pintype "passive"))
      (node (ref "Q20") (pin "3") (pinfunction "A_3") (pintype "passive"))
      (node (ref "Q24") (pin "3") (pinfunction "A_3") (pintype "passive"))
      (node (ref "Q4") (pin "1") (pinfunction "S_1") (pintype "passive"))
      (node (ref "Q4") (pin "2") (pinfunction "S_2") (pintype "passive"))
      (node (ref "Q4") (pin "3") (pinfunction "S_3") (pintype "passive"))
      (node (ref "Q4") (pin "4") (pinfunction "S_4") (pintype "passive"))
      (node (ref "Q4") (pin "5") (pinfunction "S_5") (pintype "passive"))
      (node (ref "Q4") (pin "6") (pinfunction "S_6") (pintype "passive"))
      (node (ref "R100") (pin "2") (pinfunction "2_2") (pintype "passive"))
      (node (ref "R101") (pin "2") (pinfunction "2_2") (pintype "passive"))
      (node (ref "R112") (pin "2") (pinfunction "2_2") (pintype "passive"))
      (node (ref "R45") (pin "2") (pinfunction "2_2") (pintype "passive"))
      (node (ref "R66") (pin "1") (pinfunction "1_1") (pintype "passive"))
      (node (ref "R67") (pin "1") (pinfunction "1_1") (pintype "passive"))
      (node (ref "R69") (pin "1") (pinfunction "1_1") (pintype "passive"))
      (node (ref "R7") (pin "2") (pinfunction "2_2") (pintype "passive"))
      (node (ref "R70") (pin "1") (pinfunction "1_1") (pintype "passive"))
      (node (ref "R73") (pin "1") (pinfunction "1_1") (pintype "passive"))
      (node (ref "R89") (pin "2") (pinfunction "2_2") (pintype "passive"))
      (node (ref "R93") (pin "2") (pinfunction "2_2") (pintype "passive"))
      (node (ref "R98") (pin "2") (pinfunction "2_2") (pintype "passive"))
      (node (ref "R99") (pin "2") (pinfunction "2_2") (pintype "passive"))
      (node (ref "U1") (pin "3") (pinfunction "GND_3") (pintype "passive"))
      (node (ref "U1") (pin "4") (pinfunction "GND_4") (pintype "passive"))
      (node (ref "U1") (pin "9") (pinfunction "GND_9") (pintype "passive"))
      (node (ref "U4") (pin "3") (pinfunction "GND_3") (pintype "passive"))
      (node (ref "U4") (pin "4") (pinfunction "GND_4") (pintype "passive"))
      (node (ref "U4") (pin "9") (pinfunction "GND_9") (pintype "passive"))
      (node (ref "U5") (pin "3") (pinfunction "E_3") (pintype "passive"))
      (node (ref "U6") (pin "5") (pinfunction "GND_5") (pintype "passive"))
      (node (ref "U7") (pin "2") (pinfunction "C_2") (pintype "passive"))
    )
    (net (code "112") (name "SGND") (class "Default")
      (node (ref "C14") (pin "2") (pinfunction "2_2") (pintype "passive"))
      (node (ref "C23") (pin "2") (pinfunction "2_2") (pintype "passive"))
      (node (ref "C25") (pin "2") (pinfunction "2_2") (pintype "passive"))
      (node (ref "C26") (pin "2") (pinfunction "2_2") (pintype "passive"))
      (node (ref "C27") (pin "2") (pinfunction "2_2") (pintype "passive"))
      (node (ref "C28") (pin "2") (pinfunction "2_2") (pintype "passive"))
      (node (ref "C29") (pin "2") (pinfunction "2_2") (pintype "passive"))
      (node (ref "C30") (pin "2") (pinfunction "2_2") (pintype "passive"))
      (node (ref "C36") (pin "2") (pinfunction "2_2") (pintype "passive"))
      (node (ref "C37") (pin "2") (pinfunction "2_2") (pintype "passive"))
      (node (ref "C38") (pin "2") (pinfunction "2_2") (pintype "passive"))
      (node (ref "C49") (pin "2") (pinfunction "2_2") (pintype "passive"))
      (node (ref "C51") (pin "2") (pinfunction "2_2") (pintype "passive"))
      (node (ref "C53") (pin "2") (pinfunction "2_2") (pintype "passive"))
      (node (ref "C56") (pin "1") (pinfunction "1_1") (pintype "passive"))
      (node (ref "C57") (pin "1") (pinfunction "1_1") (pintype "passive"))
      (node (ref "C7") (pin "2") (pinfunction "2_2") (pintype "passive"))
      (node (ref "D3") (pin "1") (pinfunction "A_1") (pintype "passive"))
      (node (ref "D8") (pin "1") (pinfunction "A_1") (pintype "passive"))
      (node (ref "Q10") (pin "2") (pinfunction "S_2") (pintype "passive"))
      (node (ref "Q12") (pin "2") (pinfunction "S_2") (pintype "passive"))
      (node (ref "Q13") (pin "2") (pinfunction "E_2") (pintype "passive"))
      (node (ref "Q14") (pin "2") (pinfunction "S_2") (pintype "passive"))
      (node (ref "Q17") (pin "2") (pinfunction "S_2") (pintype "passive"))
      (node (ref "Q19") (pin "3") (pinfunction "A_3") (pintype "passive"))
      (node (ref "Q2") (pin "1") (pinfunction "S_1") (pintype "passive"))
      (node (ref "Q2") (pin "2") (pinfunction "S_2") (pintype "passive"))
      (node (ref "Q2") (pin "3") (pinfunction "S_3") (pintype "passive"))
      (node (ref "Q21") (pin "2") (pinfunction "E_2") (pintype "passive"))
      (node (ref "Q22") (pin "2") (pinfunction "S_2") (pintype "passive"))
      (node (ref "Q3") (pin "1") (pinfunction "S_1") (pintype "passive"))
      (node (ref "Q3") (pin "2") (pinfunction "S_2") (pintype "passive"))
      (node (ref "Q3") (pin "3") (pinfunction "S_3") (pintype "passive"))
      (node (ref "Q5") (pin "1") (pinfunction "S_1") (pintype "passive"))
      (node (ref "Q5") (pin "2") (pinfunction "S_2") (pintype "passive"))
      (node (ref "Q5") (pin "3") (pinfunction "S_3") (pintype "passive"))
      (node (ref "Q6") (pin "1") (pinfunction "S_1") (pintype "passive"))
      (node (ref "Q6") (pin "2") (pinfunction "S_2") (pintype "passive"))
      (node (ref "Q6") (pin "3") (pinfunction "S_3") (pintype "passive"))
      (node (ref "Q7") (pin "2") (pinfunction "S_2") (pintype "passive"))
      (node (ref "R102") (pin "1") (pinfunction "1_1") (pintype "passive"))
      (node (ref "R106") (pin "1") (pinfunction "1_1") (pintype "passive"))
      (node (ref "R108") (pin "1") (pinfunction "1_1") (pintype "passive"))
      (node (ref "R12") (pin "1") (pinfunction "1_1") (pintype "passive"))
      (node (ref "R13") (pin "1") (pinfunction "1_1") (pintype "passive"))
      (node (ref "R14") (pin "1") (pinfunction "1_1") (pintype "passive"))
      (node (ref "R15") (pin "1") (pinfunction "1_1") (pintype "passive"))
      (node (ref "R16") (pin "1") (pinfunction "1_1") (pintype "passive"))
      (node (ref "R17") (pin "1") (pinfunction "1_1") (pintype "passive"))
      (node (ref "R18") (pin "1") (pinfunction "1_1") (pintype "passive"))
      (node (ref "R19") (pin "1") (pinfunction "1_1") (pintype "passive"))
      (node (ref "R20") (pin "1") (pinfunction "1_1") (pintype "passive"))
      (node (ref "R21") (pin "1") (pinfunction "1_1") (pintype "passive"))
      (node (ref "R22") (pin "1") (pinfunction "1_1") (pintype "passive"))
      (node (ref "R23") (pin "1") (pinfunction "1_1") (pintype "passive"))
      (node (ref "R25") (pin "2") (pinfunction "2_2") (pintype "passive"))
      (node (ref "R26") (pin "2") (pinfunction "2_2") (pintype "passive"))
      (node (ref "R49") (pin "2") (pinfunction "2_2") (pintype "passive"))
      (node (ref "R5") (pin "2") (pinfunction "2_2") (pintype "passive"))
      (node (ref "R6") (pin "2") (pinfunction "2_2") (pintype "passive"))
      (node (ref "R65") (pin "2") (pinfunction "2_2") (pintype "passive"))
      (node (ref "R74") (pin "2") (pinfunction "2_2") (pintype "passive"))
      (node (ref "R90") (pin "2") (pinfunction "2_2") (pintype "passive"))
      (node (ref "R91") (pin "1") (pinfunction "1_1") (pintype "passive"))
      (node (ref "U2") (pin "2") (pinfunction "GND_2") (pintype "passive"))
      (node (ref "U2") (pin "4") (pinfunction "SSB_4") (pintype "passive"))
      (node (ref "U2") (pin "5") (pinfunction "SSA_5") (pintype "passive"))
      (node (ref "U2") (pin "9") (pinfunction "EP_9") (pintype "passive"))
      (node (ref "U3") (pin "2") (pinfunction "GND_2") (pintype "passive"))
    )
    (net (code "113") (name "VCC3") (class "Default")
      (node (ref "U8") (pin "4") (pinfunction "C_4") (pintype "passive"))
    )
    (net (code "114") (name "VCC_GD") (class "Default")
      (node (ref "C1") (pin "1") (pinfunction "1_1") (pintype "passive"))
      (node (ref "C15") (pin "1") (pinfunction "1_1") (pintype "passive"))
      (node (ref "C16") (pin "1") (pinfunction "1_1") (pintype "passive"))
      (node (ref "C2") (pin "1") (pinfunction "1_1") (pintype "passive"))
      (node (ref "C41") (pin "1") (pinfunction "1_1") (pintype "passive"))
      (node (ref "C42") (pin "1") (pinfunction "1_1") (pintype "passive"))
      (node (ref "D1") (pin "1") (pinfunction "A_1") (pintype "passive"))
      (node (ref "D2") (pin "1") (pinfunction "A_1") (pintype "passive"))
      (node (ref "Q16") (pin "3") (pinfunction "D_3") (pintype "passive"))
      (node (ref "R3") (pin "2") (pinfunction "2_2") (pintype "passive"))
      (node (ref "R50") (pin "2") (pinfunction "2_2") (pintype "passive"))
      (node (ref "U1") (pin "1") (pinfunction "VCC_1") (pintype "passive"))
      (node (ref "U4") (pin "1") (pinfunction "VCC_1") (pintype "passive"))
    )
    (net (code "115") (name "VCC_IC") (class "Default")
      (node (ref "C48") (pin "1") (pinfunction "1_1") (pintype "passive"))
      (node (ref "C60") (pin "1") (pinfunction "1_1") (pintype "passive"))
      (node (ref "D5") (pin "2") (pinfunction "K_2") (pintype "passive"))
      (node (ref "Q16") (pin "2") (pinfunction "S_2") (pintype "passive"))
      (node (ref "R80") (pin "1") (pinfunction "1_1") (pintype "passive"))
      (node (ref "R86") (pin "1") (pinfunction "1_1") (pintype "passive"))
      (node (ref "R87") (pin "2") (pinfunction "2_2") (pintype "passive"))
      (node (ref "U6") (pin "4") (pinfunction "VCC_4") (pintype "passive"))
      (node (ref "U8") (pin "3") (pinfunction "E_3") (pintype "passive"))
    )
    (net (code "116") (name "VRECT_NEG") (class "Default")
      (node (ref "BD1") (pin "4") (pinfunction "4_4") (pintype "passive"))
      (node (ref "C3") (pin "1") (pinfunction "1_1") (pintype "passive"))
      (node (ref "D14") (pin "2") (pinfunction "K_2") (pintype "passive"))
      (node (ref "R66") (pin "2") (pinfunction "2_2") (pintype "passive"))
      (node (ref "R67") (pin "2") (pinfunction "2_2") (pintype "passive"))
      (node (ref "R69") (pin "2") (pinfunction "2_2") (pintype "passive"))
      (node (ref "R70") (pin "2") (pinfunction "2_2") (pintype "passive"))
      (node (ref "R73") (pin "2") (pinfunction "2_2") (pintype "passive"))
      (node (ref "U6") (pin "6") (pinfunction "ISEN_6") (pintype "passive"))
    )
    (net (code "117") (name "VRECT_POS") (class "Default")
      (node (ref "BD1") (pin "1") (pinfunction "1_1") (pintype "passive"))
      (node (ref "C3") (pin "2") (pinfunction "2_2") (pintype "passive"))
      (node (ref "D10") (pin "2") (pinfunction "K_2") (pintype "passive"))
      (node (ref "D12") (pin "2") (pinfunction "K_2") (pintype "passive"))
      (node (ref "Q1") (pin "10") (pinfunction "D_10") (pintype "passive"))
      (node (ref "Q1") (pin "11") (pinfunction "D_11") (pintype "passive"))
      (node (ref "Q1") (pin "9") (pinfunction "D_9") (pintype "passive"))
      (node (ref "Q8") (pin "10") (pinfunction "D_10") (pintype "passive"))
      (node (ref "Q8") (pin "11") (pinfunction "D_11") (pintype "passive"))
      (node (ref "Q8") (pin "9") (pinfunction "D_9") (pintype "passive"))
    )
    (net (code "118") (name "unconnected-(U6-NC-Pad2)") (class "Default")
      (node (ref "U6") (pin "2") (pinfunction "NC_2") (pintype "passive+no_connect"))
    )
  )
)
